# 3_6_1--esp32_-.net
KiCad netlist of a schematic drawn in EasyEDA Pro
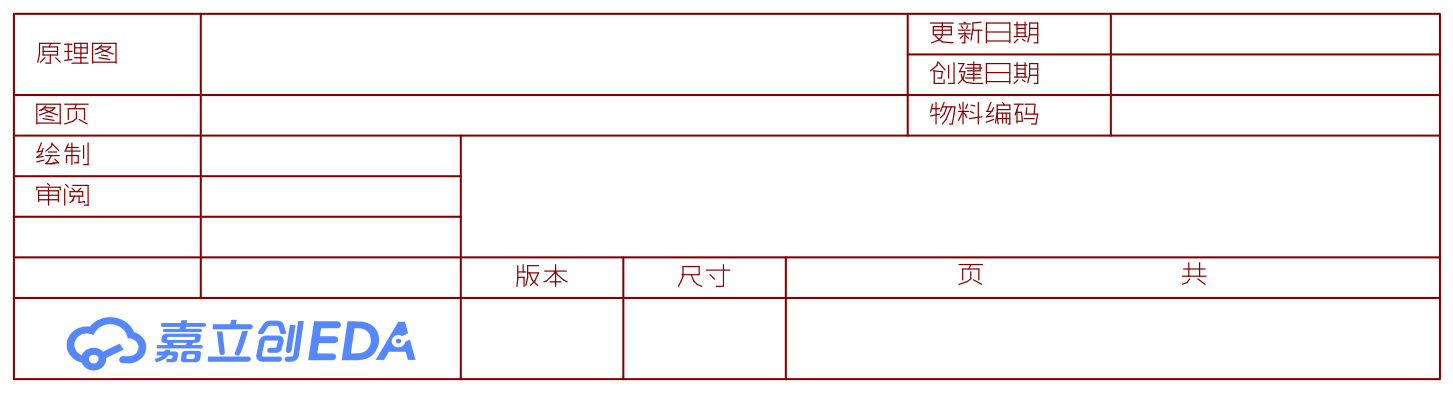
[diagram p0: 主控MCU]
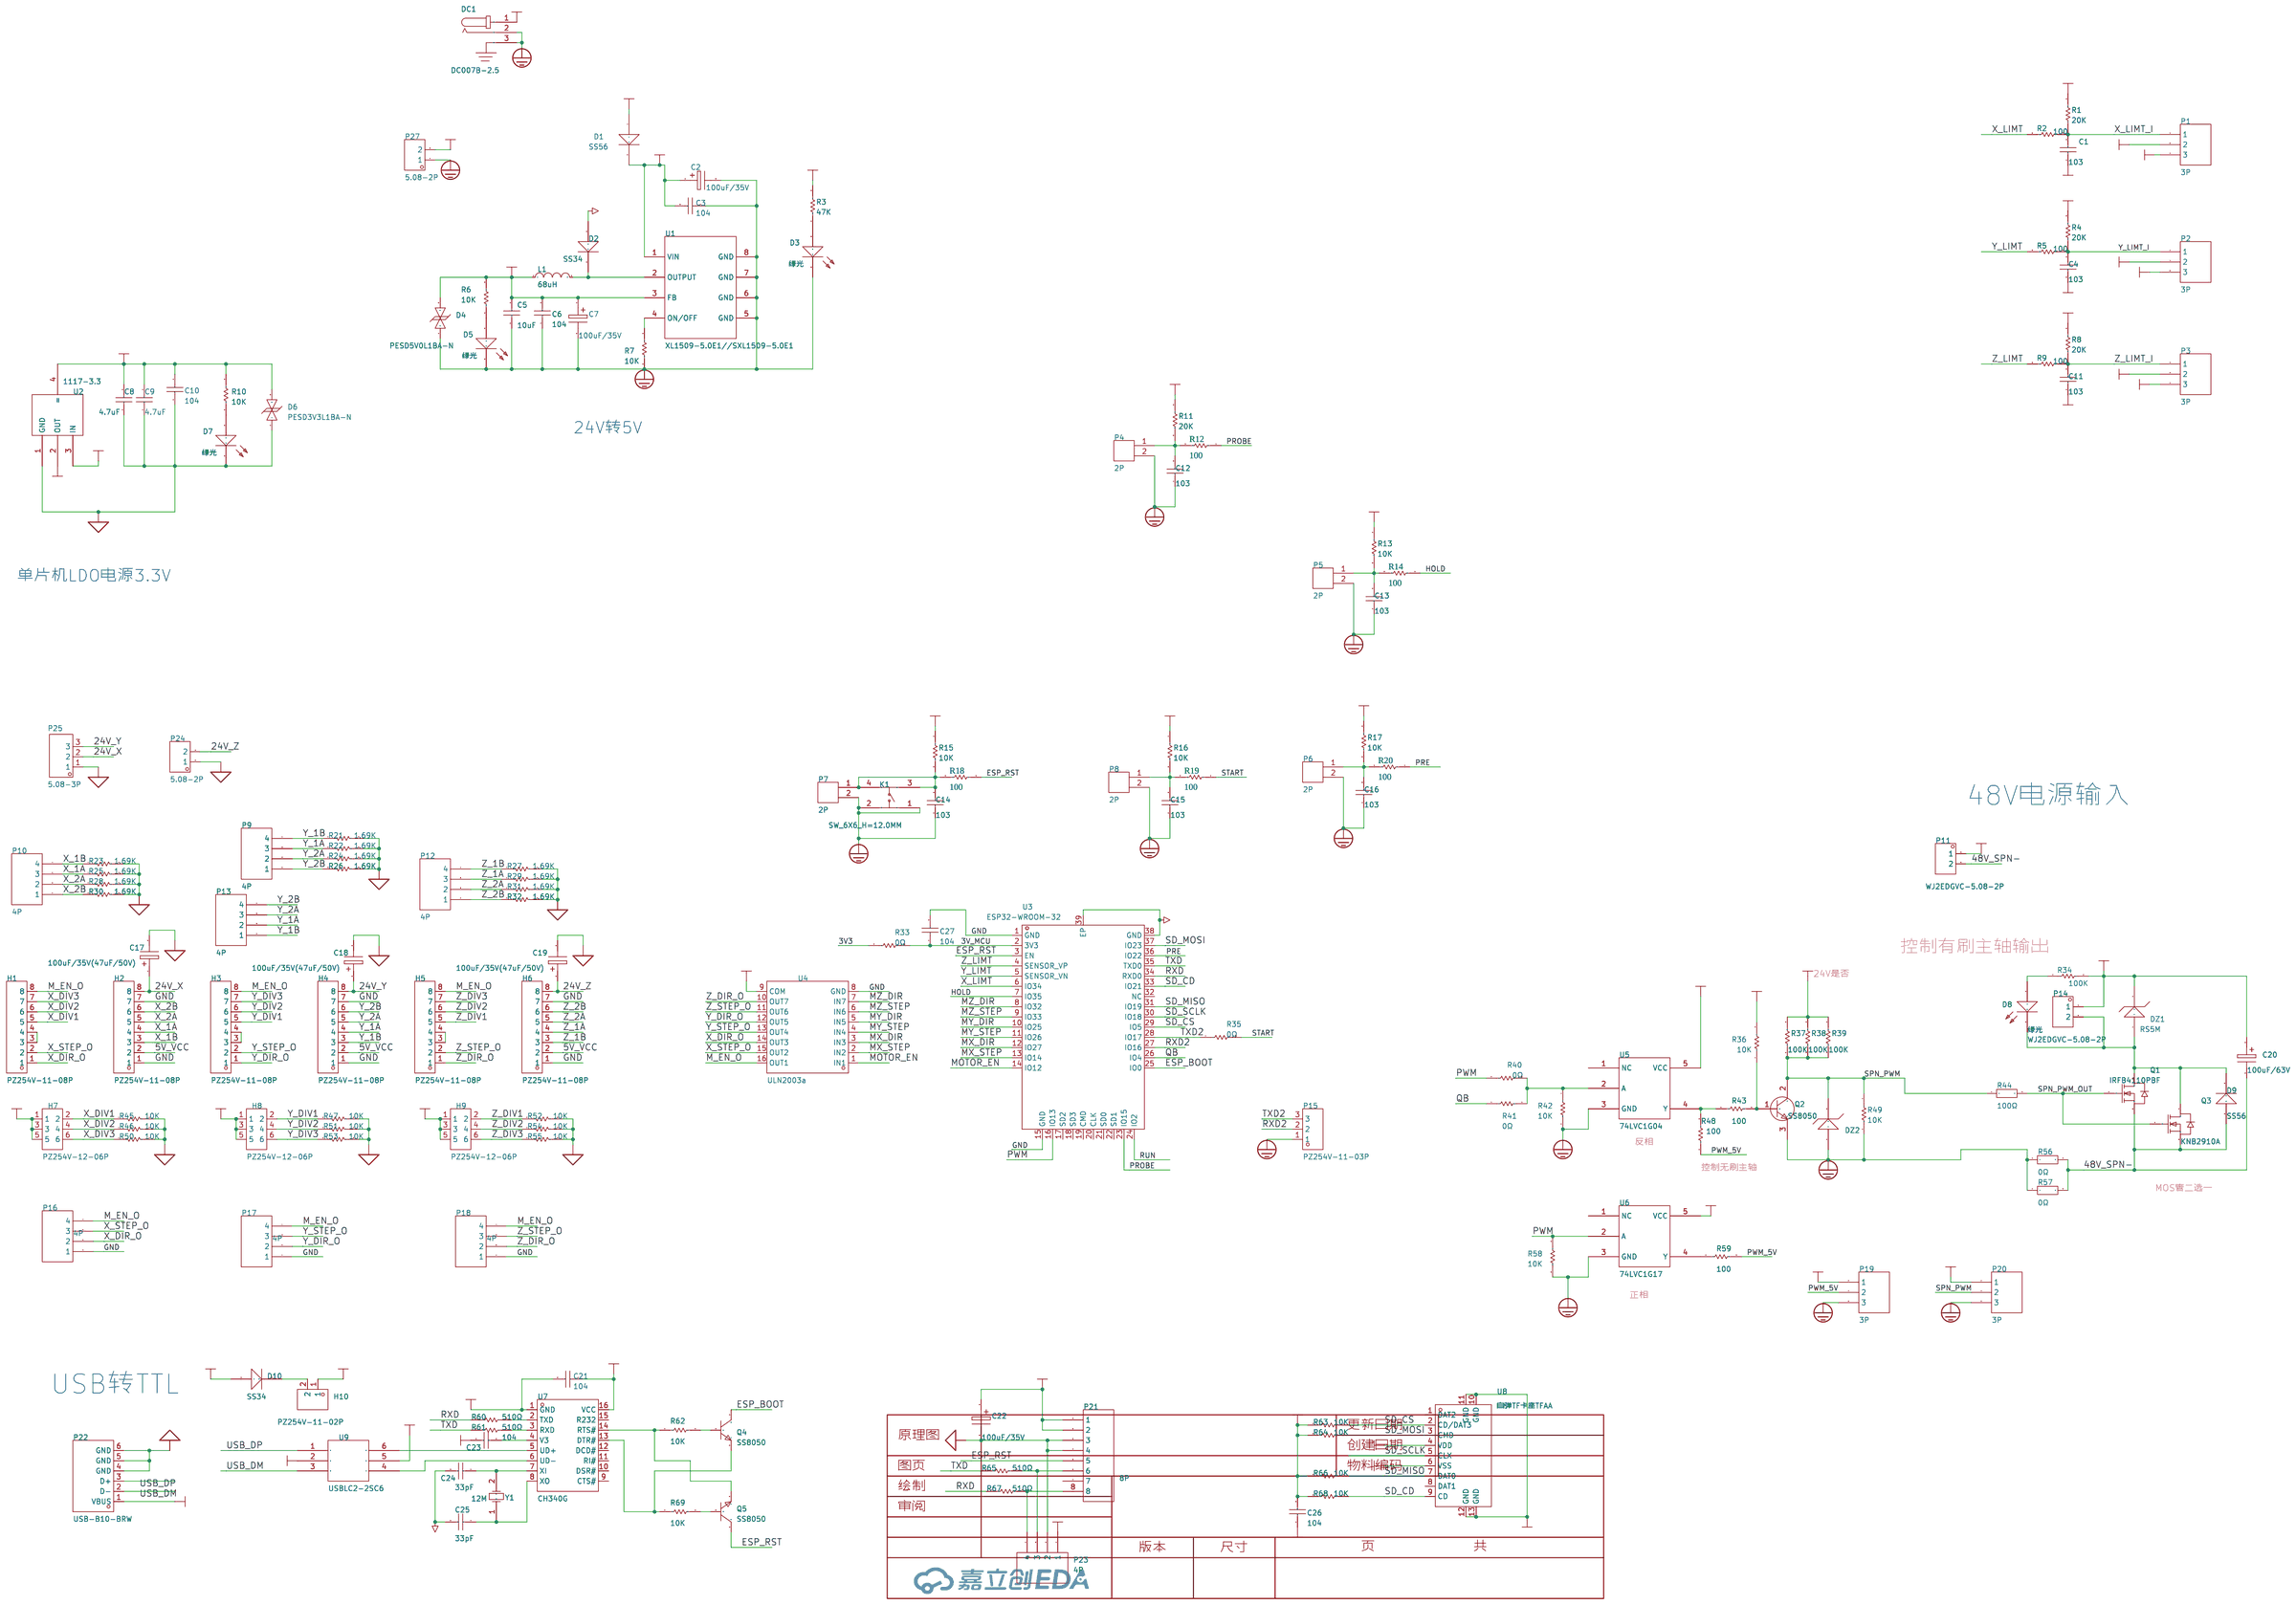
[diagram p1: 电源]

(export (version "E")
  (design (tool "Eeschema 10.0.6"))
  (components
    (comp (ref "C1") (value "103") (footprint "easyedapro:11") (libsource (lib "easyedapro") (part "CAP")))
    (comp (ref "C2")
      (value "100uF/35V")
      (footprint "easyedapro:电解电容贴片10x10")
      (libsource (lib "easyedapro") (part "ELECTRO1"))
    )
    (comp (ref "C3")
      (value "104")
      (footprint "easyedapro:0603C")
      (description "Capacitor (Semiconductor SIM Model)")
      (libsource (lib "easyedapro") (part "Cap Semi"))
    )
    (comp (ref "C4") (value "103") (footprint "easyedapro:11") (libsource (lib "easyedapro") (part "CAP")))
    (comp (ref "C5") (value "10uF") (libsource (lib "") (part "CAP_1")))
    (comp (ref "C6")
      (value "104")
      (footprint "easyedapro:0603C")
      (description "Capacitor (Semiconductor SIM Model)")
      (libsource (lib "easyedapro") (part "Cap Semi"))
    )
    (comp (ref "C7")
      (value "100uF/35V")
      (footprint "easyedapro:0603C")
      (libsource (lib "easyedapro") (part "ELECTRO1"))
    )
    (comp (ref "C8") (value "4.7uF") (libsource (lib "") (part "CAP_1")))
    (comp (ref "C9") (value "4.7uF") (libsource (lib "") (part "CAP_1")))
    (comp (ref "C10")
      (value "104")
      (footprint "easyedapro:0603C")
      (description "Capacitor (Semiconductor SIM Model)")
      (libsource (lib "easyedapro") (part "Cap Semi"))
    )
    (comp (ref "C11") (value "103") (footprint "easyedapro:11") (libsource (lib "easyedapro") (part "CAP")))
    (comp (ref "C12") (value "103") (footprint "easyedapro:11") (libsource (lib "easyedapro") (part "CAP")))
    (comp (ref "C13") (value "103") (footprint "easyedapro:11") (libsource (lib "easyedapro") (part "CAP")))
    (comp (ref "C14") (value "103") (footprint "easyedapro:11") (libsource (lib "easyedapro") (part "CAP")))
    (comp (ref "C15") (value "103") (footprint "easyedapro:11") (libsource (lib "easyedapro") (part "CAP")))
    (comp (ref "C16") (value "103") (footprint "easyedapro:11") (libsource (lib "easyedapro") (part "CAP")))
    (comp (ref "C17")
      (value "100uF/35V(47uF/50V)")
      (footprint "easyedapro:电解电容贴片10x10")
      (libsource (lib "easyedapro") (part "ELECTRO1"))
    )
    (comp (ref "C18")
      (value "100uF/35V(47uF/50V)")
      (footprint "easyedapro:电解电容贴片10x10")
      (libsource (lib "easyedapro") (part "ELECTRO1"))
    )
    (comp (ref "C19")
      (value "100uF/35V(47uF/50V)")
      (footprint "easyedapro:电解电容贴片10x10")
      (libsource (lib "easyedapro") (part "ELECTRO1"))
    )
    (comp (ref "C20")
      (value "100uF/63V")
      (footprint "easyedapro:电解电容贴片10x10")
      (libsource (lib "easyedapro") (part "ELECTRO1"))
    )
    (comp (ref "C21")
      (value "104")
      (footprint "easyedapro:0603C")
      (description "Capacitor (Semiconductor SIM Model)")
      (libsource (lib "easyedapro") (part "Cap Semi"))
    )
    (comp (ref "C22")
      (value "100uF/35V")
      (footprint "easyedapro:电解电容贴片10x10")
      (libsource (lib "easyedapro") (part "ELECTRO1"))
    )
    (comp (ref "C23")
      (value "104")
      (footprint "easyedapro:0603C")
      (description "Capacitor (Semiconductor SIM Model)")
      (libsource (lib "easyedapro") (part "Cap Semi"))
    )
    (comp (ref "C24")
      (value "18pF")
      (footprint "easyedapro:0603C")
      (description "Capacitor (Semiconductor SIM Model)")
      (libsource (lib "easyedapro") (part "Cap Semi"))
    )
    (comp (ref "C25")
      (value "18pF")
      (footprint "easyedapro:0603C")
      (description "Capacitor (Semiconductor SIM Model)")
      (libsource (lib "easyedapro") (part "Cap Semi"))
    )
    (comp (ref "C26")
      (value "104")
      (footprint "easyedapro:11")
      (description "Capacitor (Semiconductor SIM Model)")
      (libsource (lib "easyedapro") (part "Cap Semi"))
    )
    (comp (ref "C27")
      (value "104")
      (footprint "easyedapro:0603C")
      (description "Capacitor (Semiconductor SIM Model)")
      (libsource (lib "easyedapro") (part "Cap Semi"))
    )
    (comp (ref "D1")
      (value "SS56")
      (footprint "easyedapro:SMA")
      (libsource (lib "easyedapro") (part "1N4148"))
    )
    (comp (ref "D2") (value "SS34") (libsource (lib "") (part "1N4148_1")))
    (comp (ref "D3")
      (value "绿光")
      (footprint "easyedapro:0603LED")
      (libsource (lib "easyedapro") (part "LED"))
    )
    (comp (ref "D4")
      (value "PESD5V0L1BA-N")
      (footprint "easyedapro:SOD-523_L1.2-W0.8-LS1.6-BI")
      (description "极性:Bidirectional;反向关断电压（典型值）:5V (Max);击穿电压（最小值）:6V;箝位电压:15V;峰值脉冲电流（10/1000us）:5A (8/20us);")
      (fields (field (name "Manufacturer") "BORN伯恩半导体"))
      (libsource (lib "easyedapro") (part "PESD5V0S1BBN"))
    )
    (comp (ref "D5")
      (value "绿光")
      (footprint "easyedapro:0603LED")
      (libsource (lib "easyedapro") (part "LED"))
    )
    (comp (ref "D6")
      (value "PESD3V3L1BA-N")
      (footprint "easyedapro:SOD-523_L1.2-W0.8-LS1.6-BI")
      (description "极性:Bidirectional;反向关断电压（典型值）:5V (Max);击穿电压（最小值）:6V;箝位电压:15V;峰值脉冲电流（10/1000us）:5A (8/20us);")
      (fields (field (name "Manufacturer") "BORN伯恩半导体"))
      (libsource (lib "easyedapro") (part "PESD5V0S1BBN"))
    )
    (comp (ref "D7")
      (value "绿光")
      (footprint "easyedapro:0603LED")
      (libsource (lib "easyedapro") (part "LED"))
    )
    (comp (ref "D8")
      (value "绿光")
      (footprint "easyedapro:0603LED")
      (libsource (lib "easyedapro") (part "LED"))
    )
    (comp (ref "D9") (value "SS56") (libsource (lib "") (part "1N4148_1")))
    (comp (ref "D10")
      (value "SS34")
      (footprint "easyedapro:SMA")
      (libsource (lib "easyedapro") (part "1N4148"))
    )
    (comp (ref "DC1")
      (value "DC007B-2.5")
      (footprint "easyedapro:DC-IN-TH_HX-DC007B-2.5")
      (description "连接器类型:DC电源插座;安装方式:弯插;触点内径:2.5mm;触点外径:7.7mm;额定电流:5A;额定电压:20V;工作温度:-25°C~+70°C;")
      (fields (field (name "Manufacturer") "SHOU HAN(首韩)"))
      (libsource (lib "easyedapro") (part "DC007B-2.5"))
    )
    (comp (ref "DZ1") (value "RS5M") (libsource (lib "easyedapro") (part "ѹ")))
    (comp (ref "DZ2") (value "--ѹ------SMAZ10V") (libsource (lib "easyedapro") (part "ѹ")))
    (comp (ref "H1")
      (value "PZ254V-11-08P")
      (footprint "easyedapro:HDR-TH_8P-P2.54-V-M")
      (fields (field (name "Manufacturer") "XFCN(兴飞)"))
      (libsource (lib "easyedapro") (part "PZ254V-11-08P"))
    )
    (comp (ref "H2")
      (value "PZ254V-11-08P")
      (footprint "easyedapro:HDR-TH_8P-P2.54-V-M")
      (fields (field (name "Manufacturer") "XFCN(兴飞)"))
      (libsource (lib "easyedapro") (part "PZ254V-11-08P"))
    )
    (comp (ref "H3")
      (value "PZ254V-11-08P")
      (footprint "easyedapro:HDR-TH_8P-P2.54-V-M")
      (fields (field (name "Manufacturer") "XFCN(兴飞)"))
      (libsource (lib "easyedapro") (part "PZ254V-11-08P"))
    )
    (comp (ref "H4")
      (value "PZ254V-11-08P")
      (footprint "easyedapro:HDR-TH_8P-P2.54-V-M")
      (fields (field (name "Manufacturer") "XFCN(兴飞)"))
      (libsource (lib "easyedapro") (part "PZ254V-11-08P"))
    )
    (comp (ref "H5")
      (value "PZ254V-11-08P")
      (footprint "easyedapro:HDR-TH_8P-P2.54-V-M")
      (fields (field (name "Manufacturer") "XFCN(兴飞)"))
      (libsource (lib "easyedapro") (part "PZ254V-11-08P"))
    )
    (comp (ref "H6")
      (value "PZ254V-11-08P")
      (footprint "easyedapro:HDR-TH_8P-P2.54-V-M")
      (fields (field (name "Manufacturer") "XFCN(兴飞)"))
      (libsource (lib "easyedapro") (part "PZ254V-11-08P"))
    )
    (comp (ref "H7")
      (value "PZ254V-12-06P")
      (footprint "easyedapro:HDR-TH_PZ254V-12-06P-A40")
      (description "排针2.54mm间距 直插 2x03位 直针外露4mm")
      (fields (field (name "Manufacturer") "XFCN(兴飞)"))
      (libsource (lib "easyedapro") (part "PZ254V-12-06P-A40"))
    )
    (comp (ref "H8")
      (value "PZ254V-12-06P")
      (footprint "easyedapro:HDR-TH_PZ254V-12-06P-A40")
      (description "排针2.54mm间距 直插 2x03位 直针外露4mm")
      (fields (field (name "Manufacturer") "XFCN(兴飞)"))
      (libsource (lib "easyedapro") (part "PZ254V-12-06P-A40"))
    )
    (comp (ref "H9")
      (value "PZ254V-12-06P")
      (footprint "easyedapro:HDR-TH_PZ254V-12-06P-A40")
      (description "排针2.54mm间距 直插 2x03位 直针外露4mm")
      (fields (field (name "Manufacturer") "XFCN(兴飞)"))
      (libsource (lib "easyedapro") (part "PZ254V-12-06P-A40"))
    )
    (comp (ref "H10")
      (value "PZ254V-11-02P")
      (footprint "easyedapro:HDR-TH_2P-P2.54-V-M")
      (fields (field (name "Manufacturer") "XFCN(兴飞)"))
      (libsource (lib "easyedapro") (part "PZ254V-11-02P"))
    )
    (comp (ref "K1")
      (value "SW_6X6_H=12.0MM")
      (footprint "easyedapro:KEY-SMD_4P-L6.0-W6.0-P4.50-LS9.0")
      (libsource (lib "easyedapro") (part "SW_6X6_H=12.0MM"))
    )
    (comp (ref "L1")
      (value "68uH")
      (footprint "easyedapro:IND-SMD_L7.0-W7.0_SMDRI74-330MT")
      (description "电感值:33uH;精度:±20%;额定电流:960mA;饱和电流(Isat):1.8A;类型:屏蔽电感;")
      (fields (field (name "Manufacturer Part") "SMDRI74-330MT") (field (name "Manufacturer") "SXN(顺翔诺)"))
      (libsource (lib "easyedapro") (part "SMDRI74-330MT"))
    )
    (comp (ref "P1")
      (value "3P")
      (footprint "easyedapro:HDR1X3_CON")
      (libsource (lib "easyedapro") (part "3P"))
    )
    (comp (ref "P2")
      (value "3P")
      (footprint "easyedapro:HDR1X3_CON")
      (libsource (lib "easyedapro") (part "3P"))
    )
    (comp (ref "P3")
      (value "3P")
      (footprint "easyedapro:HDR1X3_CON")
      (libsource (lib "easyedapro") (part "3P"))
    )
    (comp (ref "P4") (value "2P") (libsource (lib "easyedapro") (part "2P")))
    (comp (ref "P5") (value "2P") (libsource (lib "easyedapro") (part "2P")))
    (comp (ref "P6") (value "2P") (libsource (lib "easyedapro") (part "2P")))
    (comp (ref "P7") (value "2P") (libsource (lib "easyedapro") (part "2P")))
    (comp (ref "P8") (value "2P") (libsource (lib "easyedapro") (part "2P")))
    (comp (ref "P9")
      (value "4P")
      (footprint "easyedapro:HDR1X4_CON")
      (libsource (lib "easyedapro") (part "4P"))
    )
    (comp (ref "P10")
      (value "4P")
      (footprint "easyedapro:HDR1X4_CON")
      (libsource (lib "easyedapro") (part "4P"))
    )
    (comp (ref "P11")
      (value "WJ2EDGVC-5.08-2P")
      (footprint "easyedapro:CONN-TH_WJ2EDGVC-5.08-2P")
      (fields (field (name "Manufacturer") "KANGNEX(康奈克斯电气)"))
      (libsource (lib "easyedapro") (part "WJ2EDGVC-5.08-2P"))
    )
    (comp (ref "P12")
      (value "4P")
      (footprint "easyedapro:HDR1X4_CON")
      (libsource (lib "easyedapro") (part "4P"))
    )
    (comp (ref "P13")
      (value "4P")
      (footprint "easyedapro:HDR1X4_CON")
      (libsource (lib "easyedapro") (part "4P"))
    )
    (comp (ref "P14")
      (value "WJ2EDGVC-5.08-2P")
      (footprint "easyedapro:CONN-TH_WJ2EDGVC-5.08-2P")
      (fields (field (name "Manufacturer") "KANGNEX(康奈克斯电气)"))
      (libsource (lib "easyedapro") (part "WJ2EDGVC-5.08-2P"))
    )
    (comp (ref "P15")
      (value "PZ254V-11-03P")
      (footprint "easyedapro:HDR-TH_3P-P2.54-V-M")
      (fields (field (name "Manufacturer") "XFCN(兴飞)"))
      (libsource (lib "easyedapro") (part "PZ254V-11-03P_C2937625"))
    )
    (comp (ref "P16") (value "4P") (libsource (lib "") (part "4P_1")))
    (comp (ref "P17") (value "4P") (libsource (lib "") (part "4P_1")))
    (comp (ref "P18") (value "4P") (libsource (lib "") (part "4P_1")))
    (comp (ref "P19")
      (value "3P")
      (footprint "easyedapro:HDR1X3_CON")
      (libsource (lib "easyedapro") (part "3P"))
    )
    (comp (ref "P20")
      (value "3P")
      (footprint "easyedapro:HDR1X3_CON")
      (libsource (lib "easyedapro") (part "3P"))
    )
    (comp (ref "P21") (value "8P") (footprint "easyedapro:IDC8") (libsource (lib "easyedapro") (part "8P")))
    (comp (ref "P22")
      (value "USB-B10-BRW")
      (footprint "easyedapro:USB-B-TH_USB-B10-BRW")
      (fields (field (name "Manufacturer") "XUNPU(讯普)"))
      (libsource (lib "easyedapro") (part "USB-B10-BRW"))
    )
    (comp (ref "P23")
      (value "4P")
      (footprint "easyedapro:HDR1X4_CON")
      (libsource (lib "easyedapro") (part "4P"))
    )
    (comp (ref "P24")
      (value "5.08-2P")
      (footprint "easyedapro:CONN-TH_WJ2EDGVC-5.08-2P")
      (fields (field (name "Manufacturer") "KANGNEX(康奈克斯电气)"))
      (libsource (lib "easyedapro") (part "WJ2EDGVC-5.08-2P"))
    )
    (comp (ref "P25")
      (value "5.08-3P")
      (footprint "easyedapro:CONN-TH_3P-P5.08-WJ2EDGVC-3P")
      (description "连接器类型:板端/插座-闭口;间距:5.08mm;排数:1;每排PIN数:3;安装方式:直针;颜色:绿色;")
      (fields (field (name "Manufacturer") "KANGNEX(康奈克斯电气)"))
      (libsource (lib "easyedapro") (part "WJ2EDGVC-3P"))
    )
    (comp (ref "P27")
      (value "5.08-2P")
      (footprint "easyedapro:CONN-TH_WJ2EDGVC-5.08-2P")
      (fields (field (name "Manufacturer") "KANGNEX(康奈克斯电气)"))
      (libsource (lib "easyedapro") (part "WJ2EDGVC-5.08-2P"))
    )
    (comp (ref "Q1")
      (value "IRFB4110PBF")
      (footprint "easyedapro:TO-220-3_L10.0-W4.5-P2.54-L")
      (fields (field (name "Manufacturer") "Infineon(英飞凌)"))
      (libsource (lib "easyedapro") (part "IRFB4110PBF"))
    )
    (comp (ref "Q2")
      (value "SS8050")
      (fields (field (name "Publisher") "Altium Limited"))
      (libsource (lib "easyedapro") (part "NPN"))
    )
    (comp (ref "Q3")
      (value "KNB2910A")
      (footprint "easyedapro:TO-263-2_L10.0-W9.1-P5.08-LS15.2-TL")
      (description "类型:-;漏源电压(Vdss):100V;连续漏极电流(Id):130A;导通电阻(RDS(on)):9mΩ@70V,10A;耗散功率(Pd):300W;阈值电压(Vgs(th)):4V;")
      (fields (field (name "Manufacturer") "KIA"))
      (libsource (lib "easyedapro") (part "KNB2910A"))
    )
    (comp (ref "Q4")
      (value "SS8050")
      (footprint "easyedapro:SOT-23-3_L2.9-W1.3-P1.90-LS2.4-BR")
      (fields (field (name "Manufacturer") "Doeshare(德芯)"))
      (libsource (lib "easyedapro") (part "SS8050_C2931717"))
    )
    (comp (ref "Q5")
      (value "SS8050")
      (footprint "easyedapro:SOT-23-3_L2.9-W1.3-P1.90-LS2.4-BR")
      (fields (field (name "Manufacturer") "Doeshare(德芯)"))
      (libsource (lib "easyedapro") (part "SS8050_C2931717"))
    )
    (comp (ref "R1")
      (value "20K")
      (footprint "easyedapro:10")
      (description "Resistor")
      (libsource (lib "easyedapro") (part "RES"))
    )
    (comp (ref "R2")
      (value "100")
      (footprint "easyedapro:10")
      (description "Resistor")
      (libsource (lib "easyedapro") (part "RES"))
    )
    (comp (ref "R3")
      (value "47K")
      (footprint "easyedapro:0603R")
      (description "Resistor")
      (libsource (lib "easyedapro") (part "RES"))
    )
    (comp (ref "R4")
      (value "20K")
      (footprint "easyedapro:10")
      (description "Resistor")
      (libsource (lib "easyedapro") (part "RES"))
    )
    (comp (ref "R5")
      (value "100")
      (footprint "easyedapro:10")
      (description "Resistor")
      (libsource (lib "easyedapro") (part "RES"))
    )
    (comp (ref "R6")
      (value "10K")
      (footprint "easyedapro:0603R")
      (description "Resistor")
      (libsource (lib "easyedapro") (part "RES"))
    )
    (comp (ref "R7")
      (value "10K")
      (footprint "easyedapro:0603R")
      (description "Resistor")
      (libsource (lib "easyedapro") (part "RES"))
    )
    (comp (ref "R8")
      (value "20K")
      (footprint "easyedapro:10")
      (description "Resistor")
      (libsource (lib "easyedapro") (part "RES"))
    )
    (comp (ref "R9")
      (value "100")
      (footprint "easyedapro:10")
      (description "Resistor")
      (libsource (lib "easyedapro") (part "RES"))
    )
    (comp (ref "R10")
      (value "10K")
      (footprint "easyedapro:0603R")
      (description "Resistor")
      (libsource (lib "easyedapro") (part "RES"))
    )
    (comp (ref "R11")
      (value "10K")
      (footprint "easyedapro:0603R")
      (description "Resistor")
      (libsource (lib "easyedapro") (part "RES"))
    )
    (comp (ref "R12")
      (value "100")
      (description "Resistor")
      (fields (field (name "Publisher") "Altium Limited"))
      (libsource (lib "") (part "RES_1"))
    )
    (comp (ref "R13")
      (value "10K")
      (footprint "easyedapro:0603R")
      (description "Resistor")
      (libsource (lib "easyedapro") (part "RES"))
    )
    (comp (ref "R14")
      (value "100")
      (description "Resistor")
      (fields (field (name "Publisher") "Altium Limited"))
      (libsource (lib "") (part "RES_1"))
    )
    (comp (ref "R15")
      (value "10K")
      (footprint "easyedapro:0603R")
      (description "Resistor")
      (libsource (lib "easyedapro") (part "RES"))
    )
    (comp (ref "R16")
      (value "10K")
      (footprint "easyedapro:0603R")
      (description "Resistor")
      (libsource (lib "easyedapro") (part "RES"))
    )
    (comp (ref "R17")
      (value "10K")
      (footprint "easyedapro:0603R")
      (description "Resistor")
      (libsource (lib "easyedapro") (part "RES"))
    )
    (comp (ref "R18")
      (value "100")
      (description "Resistor")
      (fields (field (name "Publisher") "Altium Limited"))
      (libsource (lib "") (part "RES_1"))
    )
    (comp (ref "R19")
      (value "100")
      (description "Resistor")
      (fields (field (name "Publisher") "Altium Limited"))
      (libsource (lib "") (part "RES_1"))
    )
    (comp (ref "R20")
      (value "100")
      (description "Resistor")
      (fields (field (name "Publisher") "Altium Limited"))
      (libsource (lib "") (part "RES_1"))
    )
    (comp (ref "R21")
      (value "10K")
      (footprint "easyedapro:0603R")
      (description "Resistor")
      (libsource (lib "easyedapro") (part "10K"))
    )
    (comp (ref "R22")
      (value "10K")
      (footprint "easyedapro:0603R")
      (description "Resistor")
      (libsource (lib "easyedapro") (part "10K"))
    )
    (comp (ref "R23")
      (value "10K")
      (footprint "easyedapro:0603R")
      (description "Resistor")
      (libsource (lib "easyedapro") (part "10K"))
    )
    (comp (ref "R24")
      (value "10K")
      (footprint "easyedapro:0603R")
      (description "Resistor")
      (libsource (lib "easyedapro") (part "10K"))
    )
    (comp (ref "R25")
      (value "10K")
      (footprint "easyedapro:0603R")
      (description "Resistor")
      (libsource (lib "easyedapro") (part "10K"))
    )
    (comp (ref "R26")
      (value "10K")
      (footprint "easyedapro:0603R")
      (description "Resistor")
      (libsource (lib "easyedapro") (part "10K"))
    )
    (comp (ref "R27")
      (value "10K")
      (footprint "easyedapro:0603R")
      (description "Resistor")
      (libsource (lib "easyedapro") (part "10K"))
    )
    (comp (ref "R28")
      (value "10K")
      (footprint "easyedapro:0603R")
      (description "Resistor")
      (libsource (lib "easyedapro") (part "10K"))
    )
    (comp (ref "R29")
      (value "10K")
      (footprint "easyedapro:0603R")
      (description "Resistor")
      (libsource (lib "easyedapro") (part "10K"))
    )
    (comp (ref "R30")
      (value "10K")
      (footprint "easyedapro:0603R")
      (description "Resistor")
      (libsource (lib "easyedapro") (part "10K"))
    )
    (comp (ref "R31")
      (value "10K")
      (footprint "easyedapro:0603R")
      (description "Resistor")
      (libsource (lib "easyedapro") (part "10K"))
    )
    (comp (ref "R32")
      (value "10K")
      (footprint "easyedapro:0603R")
      (description "Resistor")
      (libsource (lib "easyedapro") (part "10K"))
    )
    (comp (ref "R33")
      (value "0Ω")
      (description "Resistor")
      (fields (field (name "Publisher") "Altium Limited"))
      (libsource (lib "") (part "RES_1"))
    )
    (comp (ref "R34")
      (value "100K")
      (description "Resistor")
      (fields (field (name "Publisher") "Altium Limited"))
      (libsource (lib "") (part "RES_1"))
    )
    (comp (ref "R35")
      (value "0Ω")
      (description "Resistor")
      (fields (field (name "Publisher") "Altium Limited"))
      (libsource (lib "") (part "RES_1"))
    )
    (comp (ref "R36")
      (value "10K")
      (description "Resistor")
      (fields (field (name "Publisher") "Altium Limited"))
      (libsource (lib "") (part "RES_1"))
    )
    (comp (ref "R37")
      (value "100K")
      (description "Resistor")
      (fields (field (name "Publisher") "Altium Limited"))
      (libsource (lib "") (part "RES_1"))
    )
    (comp (ref "R38")
      (value "100K")
      (description "Resistor")
      (fields (field (name "Publisher") "Altium Limited"))
      (libsource (lib "") (part "RES_1"))
    )
    (comp (ref "R39")
      (value "100K")
      (description "Resistor")
      (fields (field (name "Publisher") "Altium Limited"))
      (libsource (lib "") (part "RES_1"))
    )
    (comp (ref "R40")
      (value "0Ω")
      (description "Resistor")
      (fields (field (name "Publisher") "Altium Limited"))
      (libsource (lib "") (part "RES_1"))
    )
    (comp (ref "R41")
      (value "0Ω")
      (description "Resistor")
      (fields (field (name "Publisher") "Altium Limited"))
      (libsource (lib "") (part "RES_1"))
    )
    (comp (ref "R42")
      (value "10K")
      (description "Resistor")
      (fields (field (name "Publisher") "Altium Limited"))
      (libsource (lib "") (part "RES_1"))
    )
    (comp (ref "R43")
      (value "100")
      (description "Resistor")
      (fields (field (name "Publisher") "Altium Limited"))
      (libsource (lib "") (part "RES_1"))
    )
    (comp (ref "R44")
      (value "100Ω")
      (footprint "easyedapro:R1210")
      (libsource (lib "easyedapro") (part "电阻"))
    )
    (comp (ref "R45")
      (value "10K")
      (footprint "easyedapro:0603R")
      (description "Resistor")
      (libsource (lib "easyedapro") (part "10K"))
    )
    (comp (ref "R46")
      (value "10K")
      (footprint "easyedapro:0603R")
      (description "Resistor")
      (libsource (lib "easyedapro") (part "10K"))
    )
    (comp (ref "R47")
      (value "10K")
      (footprint "easyedapro:0603R")
      (description "Resistor")
      (libsource (lib "easyedapro") (part "10K"))
    )
    (comp (ref "R48")
      (value "100")
      (description "Resistor")
      (fields (field (name "Publisher") "Altium Limited"))
      (libsource (lib "") (part "RES_1"))
    )
    (comp (ref "R49")
      (value "10K")
      (description "Resistor")
      (fields (field (name "Publisher") "Altium Limited"))
      (libsource (lib "") (part "RES_1"))
    )
    (comp (ref "R50")
      (value "10K")
      (footprint "easyedapro:0603R")
      (description "Resistor")
      (libsource (lib "easyedapro") (part "10K"))
    )
    (comp (ref "R51")
      (value "10K")
      (footprint "easyedapro:0603R")
      (description "Resistor")
      (libsource (lib "easyedapro") (part "10K"))
    )
    (comp (ref "R52")
      (value "10K")
      (footprint "easyedapro:0603R")
      (description "Resistor")
      (libsource (lib "easyedapro") (part "10K"))
    )
    (comp (ref "R53")
      (value "10K")
      (footprint "easyedapro:0603R")
      (description "Resistor")
      (libsource (lib "easyedapro") (part "10K"))
    )
    (comp (ref "R54")
      (value "10K")
      (footprint "easyedapro:0603R")
      (description "Resistor")
      (libsource (lib "easyedapro") (part "10K"))
    )
    (comp (ref "R55")
      (value "10K")
      (footprint "easyedapro:0603R")
      (description "Resistor")
      (libsource (lib "easyedapro") (part "10K"))
    )
    (comp (ref "R56") (value "0Ω") (footprint "easyedapro:R1210") (libsource (lib "easyedapro") (part "电阻")))
    (comp (ref "R57") (value "0Ω") (footprint "easyedapro:R1210") (libsource (lib "easyedapro") (part "电阻")))
    (comp (ref "R58")
      (value "10K")
      (description "Resistor")
      (fields (field (name "Publisher") "Altium Limited"))
      (libsource (lib "") (part "RES_1"))
    )
    (comp (ref "R59")
      (value "100")
      (description "Resistor")
      (fields (field (name "Publisher") "Altium Limited"))
      (libsource (lib "") (part "RES_1"))
    )
    (comp (ref "R60")
      (value "510Ω")
      (footprint "easyedapro:0603R")
      (description "Resistor")
      (libsource (lib "easyedapro") (part "RES"))
    )
    (comp (ref "R61")
      (value "510Ω")
      (footprint "easyedapro:0603R")
      (description "Resistor")
      (libsource (lib "easyedapro") (part "RES"))
    )
    (comp (ref "R62")
      (value "10K")
      (footprint "easyedapro:0603R")
      (description "Resistor")
      (libsource (lib "easyedapro") (part "RES"))
    )
    (comp (ref "R63")
      (value "10K")
      (footprint "easyedapro:10")
      (description "Resistor")
      (libsource (lib "easyedapro") (part "RES"))
    )
    (comp (ref "R64")
      (value "10K")
      (footprint "easyedapro:10")
      (description "Resistor")
      (libsource (lib "easyedapro") (part "RES"))
    )
    (comp (ref "R65")
      (value "510Ω")
      (footprint "easyedapro:0603R")
      (description "Resistor")
      (libsource (lib "easyedapro") (part "RES"))
    )
    (comp (ref "R66")
      (value "10K")
      (footprint "easyedapro:10")
      (description "Resistor")
      (libsource (lib "easyedapro") (part "RES"))
    )
    (comp (ref "R67")
      (value "510Ω")
      (footprint "easyedapro:0603R")
      (description "Resistor")
      (libsource (lib "easyedapro") (part "RES"))
    )
    (comp (ref "R68")
      (value "10K")
      (footprint "easyedapro:10")
      (description "Resistor")
      (libsource (lib "easyedapro") (part "RES"))
    )
    (comp (ref "R69")
      (value "10K")
      (footprint "easyedapro:0603R")
      (description "Resistor")
      (libsource (lib "easyedapro") (part "RES"))
    )
    (comp (ref "U1")
      (value "XL1509-5.0E1//SXL1509-5.0E1")
      (footprint "easyedapro:SOIC-8_L5.0-W4.0-P1.27-LS6.0-BL")
      (description "功能类型:降压型;同步整流:-;输出通道数:-;拓扑结构:-;输入电压:-;输出电流(最大值):-;开关频率:-;")
      (fields (field (name "Manufacturer") "XLSEMI(芯龙)"))
      (libsource (lib "easyedapro") (part "XL1509-5.0E1"))
    )
    (comp (ref "U2")
      (value "1117-3.3")
      (footprint "easyedapro:SOT-223")
      (libsource (lib "easyedapro") (part "LM1117"))
    )
    (comp (ref "U3")
      (value "ESP32-WROOM-32")
      (footprint "easyedapro:WIFIM-SMD_ESP-WROOM-32")
      (description "WiFi+双模蓝牙 双核CPU 网口 顶配MCU 低功耗蓝牙 ESP32系列ESP-WROOM-32模组/ESP-32S 4MB")
      (fields (field (name "Manufacturer") "ESPRESSIF(乐鑫)"))
      (libsource (lib "easyedapro") (part "ESP-WROOM-32"))
    )
    (comp (ref "U4")
      (value "ULN2003a")
      (footprint "easyedapro:SOP-16_L9.9-W3.9-P1.27-LS6.0-BL")
      (description "通道数:七路;集射击穿电压(Vceo):50V;集电极电流(Ic):500mA;")
      (fields (field (name "Manufacturer") "GR(国睿)"))
      (libsource (lib "easyedapro") (part "ULN2003_C18164408"))
    )
    (comp (ref "U5")
      (value "74LVC1G04")
      (footprint "easyedapro:SMD8")
      (libsource (lib "easyedapro") (part "74LVC1G04"))
    )
    (comp (ref "U6")
      (value "74LVC1G17")
      (footprint "easyedapro:SMD8")
      (libsource (lib "easyedapro") (part "74LVC1G04"))
    )
    (comp (ref "U7")
      (value "CH340G")
      (footprint "easyedapro:SOIC-16_L9.9-W3.9-P1.27-LS6.0-BL")
      (description "应用功能:收发器;接口协议:USB 2.0;数据速率:2Mbps;")
      (fields (field (name "Manufacturer") "WCH(南京沁恒)"))
      (libsource (lib "easyedapro") (part "CH340G"))
    )
    (comp (ref "U8")
      (value "自弹TF卡座TFAA")
      (footprint "easyedapro:SIM-SMD_C9900015645")
      (libsource (lib "easyedapro") (part "自弹TF卡座TFAA"))
    )
    (comp (ref "U9")
      (value "USBLC2-2SC6")
      (footprint "easyedapro:SOT-23-6")
      (libsource (lib "easyedapro") (part "DIP6"))
    )
    (comp (ref "Y1")
      (value "12M")
      (footprint "easyedapro:晶振贴片49SSMD")
      (description "Crystal Oscillator")
      (libsource (lib "easyedapro") (part "XTAL"))
    )
  )
  (nets
    (net (code "1") (name "3V3") (class "Default")
      (node (ref "C10") (pin "2") (pinfunction "2_2") (pintype "unspecified"))
      (node (ref "C26") (pin "2") (pinfunction "2_2") (pintype "unspecified"))
      (node (ref "C8") (pin "2") (pinfunction "2_2") (pintype "input"))
      (node (ref "C9") (pin "2") (pinfunction "2_2") (pintype "input"))
      (node (ref "D6") (pin "2") (pinfunction "2_2") (pintype "input"))
      (node (ref "R10") (pin "2") (pinfunction "2_2") (pintype "unspecified"))
      (node (ref "R13") (pin "1") (pinfunction "1_1") (pintype "unspecified"))
      (node (ref "R15") (pin "1") (pinfunction "1_1") (pintype "unspecified"))
      (node (ref "R33") (pin "1") (pinfunction "1_1") (pintype "input"))
      (node (ref "R63") (pin "2") (pinfunction "2_2") (pintype "unspecified"))
      (node (ref "R64") (pin "2") (pinfunction "2_2") (pintype "unspecified"))
      (node (ref "R66") (pin "2") (pinfunction "2_2") (pintype "unspecified"))
      (node (ref "R68") (pin "2") (pinfunction "2_2") (pintype "unspecified"))
      (node (ref "U2") (pin "2") (pinfunction "OUT_2") (pintype "unspecified"))
      (node (ref "U2") (pin "4") (pinfunction "=_4") (pintype "unspecified"))
      (node (ref "U8") (pin "4") (pinfunction "VDD_4") (pintype "unspecified"))
    )
    (net (code "2") (name "3V_MCU") (class "Default")
      (node (ref "C27") (pin "1") (pinfunction "1_1") (pintype "unspecified"))
      (node (ref "R16") (pin "1") (pinfunction "1_1") (pintype "unspecified"))
      (node (ref "R17") (pin "1") (pinfunction "1_1") (pintype "unspecified"))
      (node (ref "R33") (pin "2") (pinfunction "2_2") (pintype "input"))
      (node (ref "U3") (pin "2") (pinfunction "3V3_2") (pintype "unspecified"))
    )
    (net (code "3") (name "5V_VCC") (class "Default")
      (node (ref "C21") (pin "1") (pinfunction "1_1") (pintype "unspecified"))
      (node (ref "C22") (pin "1") (pintype "unspecified"))
      (node (ref "C5") (pin "1") (pinfunction "1_1") (pintype "input"))
      (node (ref "C6") (pin "2") (pinfunction "2_2") (pintype "unspecified"))
      (node (ref "C7") (pin "1") (pintype "unspecified"))
      (node (ref "D4") (pin "2") (pinfunction "2_2") (pintype "input"))
      (node (ref "H10") (pin "1") (pinfunction "1_1") (pintype "unspecified"))
      (node (ref "H2") (pin "2") (pinfunction "2_2") (pintype "unspecified"))
      (node (ref "H4") (pin "2") (pinfunction "2_2") (pintype "unspecified"))
      (node (ref "H6") (pin "2") (pinfunction "2_2") (pintype "unspecified"))
      (node (ref "H7") (pin "1") (pinfunction "1_1") (pintype "unspecified"))
      (node (ref "H7") (pin "3") (pinfunction "3_3") (pintype "unspecified"))
      (node (ref "H7") (pin "5") (pinfunction "5_5") (pintype "unspecified"))
      (node (ref "H8") (pin "1") (pinfunction "1_1") (pintype "unspecified"))
      (node (ref "H8") (pin "3") (pinfunction "3_3") (pintype "unspecified"))
      (node (ref "H8") (pin "5") (pinfunction "5_5") (pintype "unspecified"))
      (node (ref "H9") (pin "1") (pinfunction "1_1") (pintype "unspecified"))
      (node (ref "H9") (pin "3") (pinfunction "3_3") (pintype "unspecified"))
      (node (ref "H9") (pin "5") (pinfunction "5_5") (pintype "unspecified"))
      (node (ref "L1") (pin "1") (pinfunction "1_1") (pintype "unspecified"))
      (node (ref "P1") (pin "3") (pinfunction "3_3") (pintype "unspecified"))
      (node (ref "P19") (pin "1") (pinfunction "1_1") (pintype "unspecified"))
      (node (ref "P2") (pin "3") (pinfunction "3_3") (pintype "unspecified"))
      (node (ref "P20") (pin "1") (pinfunction "1_1") (pintype "unspecified"))
      (node (ref "P21") (pin "1") (pinfunction "1_1") (pintype "unspecified"))
      (node (ref "P21") (pin "2") (pinfunction "2_2") (pintype "unspecified"))
      (node (ref "P23") (pin "1") (pinfunction "1_1") (pintype "unspecified"))
      (node (ref "P3") (pin "3") (pinfunction "3_3") (pintype "unspecified"))
      (node (ref "R1") (pin "2") (pinfunction "2_2") (pintype "unspecified"))
      (node (ref "R11") (pin "1") (pinfunction "1_1") (pintype "unspecified"))
      (node (ref "R36") (pin "2") (pinfunction "2_2") (pintype "input"))
      (node (ref "R4") (pin "2") (pinfunction "2_2") (pintype "unspecified"))
      (node (ref "R6") (pin "2") (pinfunction "2_2") (pintype "unspecified"))
      (node (ref "R8") (pin "2") (pinfunction "2_2") (pintype "unspecified"))
      (node (ref "U1") (pin "3") (pinfunction "FB_3") (pintype "input"))
      (node (ref "U2") (pin "3") (pinfunction "IN_3") (pintype "unspecified"))
      (node (ref "U4") (pin "9") (pinfunction "COM_9") (pintype "unspecified"))
      (node (ref "U5") (pin "5") (pinfunction "VCC_5") (pintype "unspecified"))
      (node (ref "U6") (pin "5") (pinfunction "VCC_5") (pintype "unspecified"))
      (node (ref "U7") (pin "16") (pinfunction "VCC_16") (pintype "unspecified"))
    )
    (net (code "4") (name "24V") (class "Default")
      (node (ref "D1") (pin "1") (pinfunction "1_1") (pintype "unspecified"))
      (node (ref "DC1") (pin "1") (pinfunction "1_1") (pintype "unspecified"))
      (node (ref "P27") (pin "2") (pinfunction "2_2") (pintype "unspecified"))
      (node (ref "R3") (pin "2") (pinfunction "2_2") (pintype "unspecified"))
      (node (ref "R37") (pin "2") (pinfunction "2_2") (pintype "input"))
      (node (ref "R38") (pin "2") (pinfunction "2_2") (pintype "input"))
      (node (ref "R39") (pin "2") (pinfunction "2_2") (pintype "input"))
    )
    (net (code "5") (name "24V_X") (class "Default")
      (node (ref "C17") (pin "1") (pintype "unspecified"))
      (node (ref "H2") (pin "8") (pinfunction "8_8") (pintype "unspecified"))
      (node (ref "P25") (pin "2") (pinfunction "2_2") (pintype "input"))
    )
    (net (code "6") (name "24V_Y") (class "Default")
      (node (ref "C18") (pin "1") (pintype "unspecified"))
      (node (ref "H4") (pin "8") (pinfunction "8_8") (pintype "unspecified"))
      (node (ref "P25") (pin "3") (pinfunction "3_3") (pintype "input"))
    )
    (net (code "7") (name "24V_Z") (class "Default")
      (node (ref "C19") (pin "1") (pintype "unspecified"))
      (node (ref "H6") (pin "8") (pinfunction "8_8") (pintype "unspecified"))
      (node (ref "P24") (pin "2") (pinfunction "2_2") (pintype "unspecified"))
    )
    (net (code "8") (name "48V_SPN+") (class "Default")
      (node (ref "C20") (pin "1") (pintype "unspecified"))
      (node (ref "DZ1") (pin "2") (pinfunction "2_2") (pintype "input"))
      (node (ref "P11") (pin "1") (pinfunction "1_1") (pintype "unspecified"))
      (node (ref "P14") (pin "1") (pinfunction "1_1") (pintype "unspecified"))
      (node (ref "R34") (pin "2") (pinfunction "2_2") (pintype "input"))
    )
    (net (code "9") (name "48V_SPN-") (class "Default")
      (node (ref "C20") (pin "2") (pintype "unspecified"))
      (node (ref "D9") (pin "1") (pinfunction "1_1") (pintype "input"))
      (node (ref "P11") (pin "2") (pinfunction "2_2") (pintype "unspecified"))
      (node (ref "Q1") (pin "3") (pinfunction "S_3") (pintype "unspecified"))
      (node (ref "Q3") (pin "3") (pinfunction "S_3") (pintype "unspecified"))
      (node (ref "R56") (pin "2") (pinfunction "2_2") (pintype "input"))
      (node (ref "R57") (pin "2") (pinfunction "2_2") (pintype "input"))
    )
    (net (code "10") (name "ESP_BOOT") (class "Default")
      (node (ref "Q4") (pin "3") (pinfunction "C_3") (pintype "unspecified"))
      (node (ref "U3") (pin "25") (pinfunction "IO0_25") (pintype "unspecified"))
    )
    (net (code "11") (name "ESP_RST") (class "Default")
      (node (ref "P21") (pin "5") (pinfunction "5_5") (pintype "unspecified"))
      (node (ref "Q5") (pin "3") (pinfunction "C_3") (pintype "unspecified"))
      (node (ref "R18") (pin "1") (pinfunction "1_1") (pintype "input"))
      (node (ref "U3") (pin "3") (pinfunction "EN_3") (pintype "unspecified"))
    )
    (net (code "12") (name "GND") (class "Default")
      (node (ref "C1") (pin "1") (pinfunction "1_1") (pintype "unspecified"))
      (node (ref "C10") (pin "1") (pinfunction "1_1") (pintype "unspecified"))
      (node (ref "C11") (pin "1") (pinfunction "1_1") (pintype "unspecified"))
      (node (ref "C12") (pin "1") (pinfunction "1_1") (pintype "unspecified"))
      (node (ref "C13") (pin "1") (pinfunction "1_1") (pintype "unspecified"))
      (node (ref "C14") (pin "1") (pinfunction "1_1") (pintype "unspecified"))
      (node (ref "C15") (pin "1") (pinfunction "1_1") (pintype "unspecified"))
      (node (ref "C16") (pin "1") (pinfunction "1_1") (pintype "unspecified"))
      (node (ref "C17") (pin "2") (pintype "unspecified"))
      (node (ref "C18") (pin "2") (pintype "unspecified"))
      (node (ref "C19") (pin "2") (pintype "unspecified"))
      (node (ref "C2") (pin "2") (pintype "unspecified"))
      (node (ref "C21") (pin "2") (pinfunction "2_2") (pintype "unspecified"))
      (node (ref "C22") (pin "2") (pintype "unspecified"))
      (node (ref "C23") (pin "2") (pinfunction "2_2") (pintype "unspecified"))
      (node (ref "C24") (pin "2") (pinfunction "2_2") (pintype "unspecified"))
      (node (ref "C25") (pin "2") (pinfunction "2_2") (pintype "unspecified"))
      (node (ref "C26") (pin "1") (pinfunction "1_1") (pintype "unspecified"))
      (node (ref "C27") (pin "2") (pinfunction "2_2") (pintype "unspecified"))
      (node (ref "C3") (pin "1") (pinfunction "1_1") (pintype "unspecified"))
      (node (ref "C4") (pin "1") (pinfunction "1_1") (pintype "unspecified"))
      (node (ref "C5") (pin "2") (pinfunction "2_2") (pintype "input"))
      (node (ref "C6") (pin "1") (pinfunction "1_1") (pintype "unspecified"))
      (node (ref "C7") (pin "2") (pintype "unspecified"))
      (node (ref "C8") (pin "1") (pinfunction "1_1") (pintype "input"))
      (node (ref "C9") (pin "1") (pinfunction "1_1") (pintype "input"))
      (node (ref "D2") (pin "1") (pinfunction "1_1") (pintype "input"))
      (node (ref "D3") (pin "2") (pinfunction "2_2") (pintype "unspecified"))
      (node (ref "D4") (pin "1") (pinfunction "1_1") (pintype "input"))
      (node (ref "D5") (pin "2") (pinfunction "2_2") (pintype "unspecified"))
      (node (ref "D6") (pin "1") (pinfunction "1_1") (pintype "input"))
      (node (ref "D7") (pin "2") (pinfunction "2_2") (pintype "unspecified"))
      (node (ref "DC1") (pin "2") (pinfunction "2_2") (pintype "unspecified"))
      (node (ref "DC1") (pin "3") (pinfunction "3_3") (pintype "unspecified"))
      (node (ref "DZ2") (pin "1") (pinfunction "1_1") (pintype "input"))
      (node (ref "H2") (pin "1") (pinfunction "1_1") (pintype "unspecified"))
      (node (ref "H2") (pin "7") (pinfunction "7_7") (pintype "unspecified"))
      (node (ref "H4") (pin "1") (pinfunction "1_1") (pintype "unspecified"))
      (node (ref "H4") (pin "7") (pinfunction "7_7") (pintype "unspecified"))
      (node (ref "H6") (pin "1") (pinfunction "1_1") (pintype "unspecified"))
      (node (ref "H6") (pin "7") (pinfunction "7_7") (pintype "unspecified"))
      (node (ref "K1") (pin "1") (pinfunction "1_1") (pintype "unspecified"))
      (node (ref "K1") (pin "2") (pinfunction "2_2") (pintype "unspecified"))
      (node (ref "P1") (pin "2") (pinfunction "2_2") (pintype "unspecified"))
      (node (ref "P15") (pin "1") (pinfunction "1_1") (pintype "unspecified"))
      (node (ref "P16") (pin "1") (pinfunction "1_1") (pintype "input"))
      (node (ref "P17") (pin "1") (pinfunction "1_1") (pintype "input"))
      (node (ref "P18") (pin "1") (pinfunction "1_1") (pintype "input"))
      (node (ref "P19") (pin "3") (pinfunction "3_3") (pintype "unspecified"))
      (node (ref "P2") (pin "2") (pinfunction "2_2") (pintype "unspecified"))
      (node (ref "P20") (pin "3") (pinfunction "3_3") (pintype "unspecified"))
      (node (ref "P21") (pin "3") (pinfunction "3_3") (pintype "unspecified"))
      (node (ref "P21") (pin "4") (pinfunction "4_4") (pintype "unspecified"))
      (node (ref "P22") (pin "4") (pinfunction "GND_4") (pintype "unspecified"))
      (node (ref "P22") (pin "5") (pinfunction "GND_5") (pintype "unspecified"))
      (node (ref "P22") (pin "6") (pinfunction "GND_6") (pintype "unspecified"))
      (node (ref "P23") (pin "2") (pinfunction "2_2") (pintype "unspecified"))
      (node (ref "P24") (pin "1") (pinfunction "1_1") (pintype "unspecified"))
      (node (ref "P25") (pin "1") (pinfunction "1_1") (pintype "input"))
      (node (ref "P27") (pin "1") (pinfunction "1_1") (pintype "unspecified"))
      (node (ref "P3") (pin "2") (pinfunction "2_2") (pintype "unspecified"))
      (node (ref "P4") (pin "2") (pintype "input"))
      (node (ref "P5") (pin "2") (pintype "input"))
      (node (ref "P6") (pin "2") (pintype "input"))
      (node (ref "P7") (pin "2") (pintype "input"))
      (node (ref "P8") (pin "2") (pintype "input"))
      (node (ref "Q2") (pin "3") (pinfunction "E_3") (pintype "input"))
      (node (ref "R21") (pin "2") (pinfunction "2_2") (pintype "unspecified"))
      (node (ref "R22") (pin "2") (pinfunction "2_2") (pintype "unspecified"))
      (node (ref "R23") (pin "2") (pinfunction "2_2") (pintype "unspecified"))
      (node (ref "R24") (pin "2") (pinfunction "2_2") (pintype "unspecified"))
      (node (ref "R25") (pin "2") (pinfunction "2_2") (pintype "unspecified"))
      (node (ref "R26") (pin "2") (pinfunction "2_2") (pintype "unspecified"))
      (node (ref "R27") (pin "2") (pinfunction "2_2") (pintype "unspecified"))
      (node (ref "R28") (pin "2") (pinfunction "2_2") (pintype "unspecified"))
      (node (ref "R29") (pin "2") (pinfunction "2_2") (pintype "unspecified"))
      (node (ref "R30") (pin "2") (pinfunction "2_2") (pintype "unspecified"))
      (node (ref "R31") (pin "2") (pinfunction "2_2") (pintype "unspecified"))
      (node (ref "R32") (pin "2") (pinfunction "2_2") (pintype "unspecified"))
      (node (ref "R42") (pin "2") (pinfunction "2_2") (pintype "input"))
      (node (ref "R45") (pin "2") (pinfunction "2_2") (pintype "unspecified"))
      (node (ref "R46") (pin "2") (pinfunction "2_2") (pintype "unspecified"))
      (node (ref "R47") (pin "2") (pinfunction "2_2") (pintype "unspecified"))
      (node (ref "R49") (pin "2") (pinfunction "2_2") (pintype "input"))
      (node (ref "R50") (pin "2") (pinfunction "2_2") (pintype "unspecified"))
      (node (ref "R51") (pin "2") (pinfunction "2_2") (pintype "unspecified"))
      (node (ref "R52") (pin "2") (pinfunction "2_2") (pintype "unspecified"))
      (node (ref "R53") (pin "2") (pinfunction "2_2") (pintype "unspecified"))
      (node (ref "R54") (pin "2") (pinfunction "2_2") (pintype "unspecified"))
      (node (ref "R55") (pin "2") (pinfunction "2_2") (pintype "unspecified"))
      (node (ref "R56") (pin "1") (pinfunction "1_1") (pintype "input"))
      (node (ref "R57") (pin "1") (pinfunction "1_1") (pintype "input"))
      (node (ref "R58") (pin "2") (pinfunction "2_2") (pintype "input"))
      (node (ref "R7") (pin "2") (pinfunction "2_2") (pintype "unspecified"))
      (node (ref "U1") (pin "5") (pinfunction "GND_5") (pintype "input"))
      (node (ref "U1") (pin "6") (pinfunction "GND_6") (pintype "input"))
      (node (ref "U1") (pin "7") (pinfunction "GND_7") (pintype "input"))
      (node (ref "U1") (pin "8") (pinfunction "GND_8") (pintype "input"))
      (node (ref "U2") (pin "1") (pinfunction "GND_1") (pintype "unspecified"))
      (node (ref "U3") (pin "1") (pinfunction "GND_1") (pintype "unspecified"))
      (node (ref "U3") (pin "15") (pinfunction "GND_15") (pintype "unspecified"))
      (node (ref "U3") (pin "38") (pinfunction "GND_38") (pintype "unspecified"))
      (node (ref "U3") (pin "39") (pinfunction "EP_39") (pintype "unspecified"))
      (node (ref "U4") (pin "8") (pinfunction "GND_8") (pintype "unspecified"))
      (node (ref "U5") (pin "3") (pinfunction "GND_3") (pintype "unspecified"))
      (node (ref "U6") (pin "3") (pinfunction "GND_3") (pintype "unspecified"))
      (node (ref "U7") (pin "1") (pinfunction "GND_1") (pintype "unspecified"))
      (node (ref "U8") (pin "10") (pinfunction "GND_10") (pintype "unspecified"))
      (node (ref "U8") (pin "11") (pinfunction "GND_11") (pintype "unspecified"))
      (node (ref "U8") (pin "12") (pinfunction "GND_12") (pintype "unspecified"))
      (node (ref "U8") (pin "13") (pinfunction "GND_13") (pintype "unspecified"))
      (node (ref "U8") (pin "6") (pinfunction "VSS_6") (pintype "unspecified"))
      (node (ref "U9") (pin "2") (pinfunction "2_2") (pintype "unspecified"))
    )
    (net (code "13") (name "HOLD") (class "Default")
      (node (ref "R14") (pin "1") (pinfunction "1_1") (pintype "input"))
      (node (ref "U3") (pin "7") (pinfunction "IO35_7") (pintype "unspecified"))
    )
    (net (code "14") (name "MOTOR_EN") (class "Default")
      (node (ref "U3") (pin "14") (pinfunction "IO12_14") (pintype "unspecified"))
      (node (ref "U4") (pin "1") (pinfunction "IN1_1") (pintype "unspecified"))
    )
    (net (code "15") (name "MX_DIR") (class "Default")
      (node (ref "U3") (pin "12") (pinfunction "IO27_12") (pintype "unspecified"))
      (node (ref "U4") (pin "3") (pinfunction "IN3_3") (pintype "unspecified"))
    )
    (net (code "16") (name "MX_STEP") (class "Default")
      (node (ref "U3") (pin "13") (pinfunction "IO14_13") (pintype "unspecified"))
      (node (ref "U4") (pin "2") (pinfunction "IN2_2") (pintype "unspecified"))
    )
    (net (code "17") (name "MY_DIR") (class "Default")
      (node (ref "U3") (pin "10") (pinfunction "IO25_10") (pintype "unspecified"))
      (node (ref "U4") (pin "5") (pinfunction "IN5_5") (pintype "unspecified"))
    )
    (net (code "18") (name "MY_STEP") (class "Default")
      (node (ref "U3") (pin "11") (pinfunction "IO26_11") (pintype "unspecified"))
      (node (ref "U4") (pin "4") (pinfunction "IN4_4") (pintype "unspecified"))
    )
    (net (code "19") (name "MZ_DIR") (class "Default")
      (node (ref "U3") (pin "8") (pinfunction "IO32_8") (pintype "unspecified"))
      (node (ref "U4") (pin "7") (pinfunction "IN7_7") (pintype "unspecified"))
    )
    (net (code "20") (name "MZ_STEP") (class "Default")
      (node (ref "U3") (pin "9") (pinfunction "IO33_9") (pintype "unspecified"))
      (node (ref "U4") (pin "6") (pinfunction "IN6_6") (pintype "unspecified"))
    )
    (net (code "21") (name "M_EN_O") (class "Default")
      (node (ref "H1") (pin "8") (pinfunction "8_8") (pintype "unspecified"))
      (node (ref "H3") (pin "8") (pinfunction "8_8") (pintype "unspecified"))
      (node (ref "H5") (pin "8") (pinfunction "8_8") (pintype "unspecified"))
      (node (ref "P16") (pin "4") (pinfunction "4_4") (pintype "input"))
      (node (ref "P17") (pin "4") (pinfunction "4_4") (pintype "input"))
      (node (ref "P18") (pin "4") (pinfunction "4_4") (pintype "input"))
      (node (ref "U4") (pin "16") (pinfunction "OUT1_16") (pintype "unspecified"))
    )
    (net (code "22") (name "Net-(C12-Pad2)") (class "Default")
      (node (ref "C12") (pin "2") (pinfunction "2_2") (pintype "unspecified"))
      (node (ref "P4") (pin "1") (pintype "input"))
      (node (ref "R11") (pin "2") (pinfunction "2_2") (pintype "unspecified"))
      (node (ref "R12") (pin "2") (pinfunction "2_2") (pintype "input"))
    )
    (net (code "23") (name "Net-(C13-Pad2)") (class "Default")
      (node (ref "C13") (pin "2") (pinfunction "2_2") (pintype "unspecified"))
      (node (ref "P5") (pin "1") (pintype "input"))
      (node (ref "R13") (pin "2") (pinfunction "2_2") (pintype "unspecified"))
      (node (ref "R14") (pin "2") (pinfunction "2_2") (pintype "input"))
    )
    (net (code "24") (name "Net-(C14-Pad2)") (class "Default")
      (node (ref "C14") (pin "2") (pinfunction "2_2") (pintype "unspecified"))
      (node (ref "K1") (pin "3") (pinfunction "3_3") (pintype "unspecified"))
      (node (ref "K1") (pin "4") (pinfunction "4_4") (pintype "unspecified"))
      (node (ref "P7") (pin "1") (pintype "input"))
      (node (ref "R15") (pin "2") (pinfunction "2_2") (pintype "unspecified"))
      (node (ref "R18") (pin "2") (pinfunction "2_2") (pintype "input"))
    )
    (net (code "25") (name "Net-(C15-Pad2)") (class "Default")
      (node (ref "C15") (pin "2") (pinfunction "2_2") (pintype "unspecified"))
      (node (ref "P8") (pin "1") (pintype "input"))
      (node (ref "R16") (pin "2") (pinfunction "2_2") (pintype "unspecified"))
      (node (ref "R19") (pin "2") (pinfunction "2_2") (pintype "input"))
    )
    (net (code "26") (name "Net-(C16-Pad2)") (class "Default")
      (node (ref "C16") (pin "2") (pinfunction "2_2") (pintype "unspecified"))
      (node (ref "P6") (pin "1") (pintype "input"))
      (node (ref "R17") (pin "2") (pinfunction "2_2") (pintype "unspecified"))
      (node (ref "R20") (pin "2") (pinfunction "2_2") (pintype "input"))
    )
    (net (code "27") (name "Net-(D3-Pad1)") (class "Default")
      (node (ref "D3") (pin "1") (pinfunction "1_1") (pintype "unspecified"))
      (node (ref "R3") (pin "1") (pinfunction "1_1") (pintype "unspecified"))
    )
    (net (code "28") (name "Net-(D5-Pad1)") (class "Default")
      (node (ref "D5") (pin "1") (pinfunction "1_1") (pintype "unspecified"))
      (node (ref "R6") (pin "1") (pinfunction "1_1") (pintype "unspecified"))
    )
    (net (code "29") (name "Net-(D7-Pad1)") (class "Default")
      (node (ref "D7") (pin "1") (pinfunction "1_1") (pintype "unspecified"))
      (node (ref "R10") (pin "1") (pinfunction "1_1") (pintype "unspecified"))
    )
    (net (code "30") (name "Net-(D8-Pad1)") (class "Default")
      (node (ref "D8") (pin "1") (pinfunction "1_1") (pintype "unspecified"))
      (node (ref "R34") (pin "1") (pinfunction "1_1") (pintype "input"))
    )
    (net (code "31") (name "Net-(D10-Pad2)") (class "Default")
      (node (ref "D10") (pin "2") (pinfunction "2_2") (pintype "unspecified"))
      (node (ref "H10") (pin "2") (pinfunction "2_2") (pintype "unspecified"))
    )
    (net (code "32") (name "Net-(H1-Pad3)") (class "Default")
      (node (ref "H1") (pin "3") (pinfunction "3_3") (pintype "unspecified"))
      (node (ref "H1") (pin "4") (pinfunction "4_4") (pintype "unspecified"))
    )
    (net (code "33") (name "Net-(H3-Pad3)") (class "Default")
      (node (ref "H3") (pin "3") (pinfunction "3_3") (pintype "unspecified"))
      (node (ref "H3") (pin "4") (pinfunction "4_4") (pintype "unspecified"))
    )
    (net (code "34") (name "Net-(H5-Pad3)") (class "Default")
      (node (ref "H5") (pin "3") (pinfunction "3_3") (pintype "unspecified"))
      (node (ref "H5") (pin "4") (pinfunction "4_4") (pintype "unspecified"))
    )
    (net (code "35") (name "Net-(P21-Pad6)") (class "Default")
      (node (ref "P21") (pin "6") (pinfunction "6_6") (pintype "unspecified"))
      (node (ref "P23") (pin "3") (pinfunction "3_3") (pintype "unspecified"))
      (node (ref "R65") (pin "2") (pinfunction "2_2") (pintype "unspecified"))
    )
    (net (code "36") (name "Net-(P21-Pad8)") (class "Default")
      (node (ref "P21") (pin "8") (pinfunction "8_8") (pintype "unspecified"))
      (node (ref "P23") (pin "4") (pinfunction "4_4") (pintype "unspecified"))
      (node (ref "R67") (pin "2") (pinfunction "2_2") (pintype "unspecified"))
    )
    (net (code "37") (name "Net-(Q1-D)") (class "Default")
      (node (ref "D8") (pin "2") (pinfunction "2_2") (pintype "unspecified"))
      (node (ref "D9") (pin "2") (pinfunction "2_2") (pintype "input"))
      (node (ref "DZ1") (pin "1") (pinfunction "1_1") (pintype "input"))
      (node (ref "P14") (pin "2") (pinfunction "2_2") (pintype "unspecified"))
      (node (ref "Q1") (pin "2") (pinfunction "D_2") (pintype "unspecified"))
      (node (ref "Q3") (pin "4") (pinfunction "D_4") (pintype "unspecified"))
    )
    (net (code "38") (name "Net-(Q2-B)") (class "Default")
      (node (ref "Q2") (pin "1") (pinfunction "B_1") (pintype "input"))
      (node (ref "R36") (pin "1") (pinfunction "1_1") (pintype "input"))
      (node (ref "R43") (pin "2") (pinfunction "2_2") (pintype "input"))
    )
    (net (code "39") (name "Net-(Q4-B)") (class "Default")
      (node (ref "Q4") (pin "1") (pinfunction "B_1") (pintype "unspecified"))
      (node (ref "R62") (pin "2") (pinfunction "2_2") (pintype "unspecified"))
    )
    (net (code "40") (name "Net-(Q4-E)") (class "Default")
      (node (ref "Q4") (pin "2") (pinfunction "E_2") (pintype "unspecified"))
      (node (ref "R69") (pin "1") (pinfunction "1_1") (pintype "unspecified"))
      (node (ref "U7") (pin "13") (pinfunction "DTR#_13") (pintype "unspecified"))
    )
    (net (code "41") (name "Net-(Q5-B)") (class "Default")
      (node (ref "Q5") (pin "1") (pinfunction "B_1") (pintype "unspecified"))
      (node (ref "R69") (pin "2") (pinfunction "2_2") (pintype "unspecified"))
    )
    (net (code "42") (name "Net-(Q5-E)") (class "Default")
      (node (ref "Q5") (pin "2") (pinfunction "E_2") (pintype "unspecified"))
      (node (ref "R62") (pin "1") (pinfunction "1_1") (pintype "unspecified"))
      (node (ref "U7") (pin "14") (pinfunction "RTS#_14") (pintype "unspecified"))
    )
    (net (code "43") (name "Net-(U1-ON{slash}OFF)") (class "Default")
      (node (ref "R7") (pin "1") (pinfunction "1_1") (pintype "unspecified"))
      (node (ref "U1") (pin "4") (pinfunction "ON/OFF_4") (pintype "input"))
    )
    (net (code "44") (name "Net-(U1-OUTPUT)") (class "Default")
      (node (ref "D2") (pin "2") (pinfunction "2_2") (pintype "input"))
      (node (ref "L1") (pin "2") (pinfunction "2_2") (pintype "unspecified"))
      (node (ref "U1") (pin "2") (pinfunction "OUTPUT_2") (pintype "input"))
    )
    (net (code "45") (name "Net-(U5-A)") (class "Default")
      (node (ref "R40") (pin "2") (pinfunction "2_2") (pintype "input"))
      (node (ref "R41") (pin "2") (pinfunction "2_2") (pintype "input"))
      (node (ref "R42") (pin "1") (pinfunction "1_1") (pintype "input"))
      (node (ref "U5") (pin "2") (pinfunction "A_2") (pintype "unspecified"))
    )
    (net (code "46") (name "Net-(U5-Y)") (class "Default")
      (node (ref "R43") (pin "1") (pinfunction "1_1") (pintype "input"))
      (node (ref "R48") (pin "2") (pinfunction "2_2") (pintype "input"))
      (node (ref "U5") (pin "4") (pinfunction "Y_4") (pintype "unspecified"))
    )
    (net (code "47") (name "Net-(U6-Y)") (class "Default")
      (node (ref "R59") (pin "1") (pinfunction "1_1") (pintype "input"))
      (node (ref "U6") (pin "4") (pinfunction "Y_4") (pintype "unspecified"))
    )
    (net (code "48") (name "Net-(U7-RXD)") (class "Default")
      (node (ref "R61") (pin "1") (pinfunction "1_1") (pintype "unspecified"))
      (node (ref "U7") (pin "3") (pinfunction "RXD_3") (pintype "unspecified"))
    )
    (net (code "49") (name "Net-(U7-TXD)") (class "Default")
      (node (ref "R60") (pin "1") (pinfunction "1_1") (pintype "unspecified"))
      (node (ref "U7") (pin "2") (pinfunction "TXD_2") (pintype "unspecified"))
    )
    (net (code "50") (name "Net-(U7-UD+)") (class "Default")
      (node (ref "U7") (pin "5") (pinfunction "UD+_5") (pintype "unspecified"))
      (node (ref "U9") (pin "6") (pinfunction "6_6") (pintype "unspecified"))
    )
    (net (code "51") (name "Net-(U7-UD-)") (class "Default")
      (node (ref "U7") (pin "6") (pinfunction "UD-_6") (pintype "unspecified"))
      (node (ref "U9") (pin "4") (pinfunction "4_4") (pintype "unspecified"))
    )
    (net (code "52") (name "Net-(U7-V3)") (class "Default")
      (node (ref "C23") (pin "1") (pinfunction "1_1") (pintype "unspecified"))
      (node (ref "U7") (pin "4") (pinfunction "V3_4") (pintype "unspecified"))
    )
    (net (code "53") (name "Net-(U7-XI)") (class "Default")
      (node (ref "C24") (pin "1") (pinfunction "1_1") (pintype "unspecified"))
      (node (ref "U7") (pin "7") (pinfunction "XI_7") (pintype "unspecified"))
      (node (ref "Y1") (pin "2") (pinfunction "OSC2_2") (pintype "unspecified"))
    )
    (net (code "54") (name "Net-(U7-XO)") (class "Default")
      (node (ref "C25") (pin "1") (pinfunction "1_1") (pintype "unspecified"))
      (node (ref "U7") (pin "8") (pinfunction "XO_8") (pintype "unspecified"))
      (node (ref "Y1") (pin "1") (pinfunction "OSC1_1") (pintype "unspecified"))
    )
    (net (code "55") (name "PRE") (class "Default")
      (node (ref "R20") (pin "1") (pinfunction "1_1") (pintype "input"))
      (node (ref "U3") (pin "36") (pinfunction "IO22_36") (pintype "unspecified"))
    )
    (net (code "56") (name "PROBE") (class "Default")
      (node (ref "R12") (pin "1") (pinfunction "1_1") (pintype "input"))
      (node (ref "U3") (pin "23") (pinfunction "IO15_23") (pintype "unspecified"))
    )
    (net (code "57") (name "PWM") (class "Default")
      (node (ref "R40") (pin "1") (pinfunction "1_1") (pintype "input"))
      (node (ref "R58") (pin "1") (pinfunction "1_1") (pintype "input"))
      (node (ref "U3") (pin "16") (pinfunction "IO13_16") (pintype "unspecified"))
      (node (ref "U6") (pin "2") (pinfunction "A_2") (pintype "unspecified"))
    )
    (net (code "58") (name "PWM_5V") (class "Default")
      (node (ref "P19") (pin "2") (pinfunction "2_2") (pintype "unspecified"))
      (node (ref "R48") (pin "1") (pinfunction "1_1") (pintype "input"))
      (node (ref "R59") (pin "2") (pinfunction "2_2") (pintype "input"))
    )
    (net (code "59") (name "QB") (class "Default")
      (node (ref "R41") (pin "1") (pinfunction "1_1") (pintype "input"))
      (node (ref "U3") (pin "26") (pinfunction "IO4_26") (pintype "unspecified"))
    )
    (net (code "60") (name "RUN") (class "Default")
      (node (ref "U3") (pin "24") (pinfunction "IO2_24") (pintype "unspecified"))
    )
    (net (code "61") (name "RXD") (class "Default")
      (node (ref "R60") (pin "2") (pinfunction "2_2") (pintype "unspecified"))
      (node (ref "R67") (pin "1") (pinfunction "1_1") (pintype "unspecified"))
      (node (ref "U3") (pin "34") (pinfunction "RXD0_34") (pintype "unspecified"))
    )
    (net (code "62") (name "RXD2") (class "Default")
      (node (ref "P15") (pin "2") (pinfunction "2_2") (pintype "unspecified"))
      (node (ref "U3") (pin "27") (pinfunction "IO16_27") (pintype "unspecified"))
    )
    (net (code "63") (name "SD_CD") (class "Default")
      (node (ref "R68") (pin "1") (pinfunction "1_1") (pintype "unspecified"))
      (node (ref "U3") (pin "33") (pinfunction "IO21_33") (pintype "unspecified"))
      (node (ref "U8") (pin "9") (pinfunction "CD_9") (pintype "unspecified"))
    )
    (net (code "64") (name "SD_CS") (class "Default")
      (node (ref "R63") (pin "1") (pinfunction "1_1") (pintype "unspecified"))
      (node (ref "U3") (pin "29") (pinfunction "IO5_29") (pintype "unspecified"))
      (node (ref "U8") (pin "2") (pinfunction "CD/DAT3_2") (pintype "unspecified"))
    )
    (net (code "65") (name "SD_MISO") (class "Default")
      (node (ref "R66") (pin "1") (pinfunction "1_1") (pintype "unspecified"))
      (node (ref "U3") (pin "31") (pinfunction "IO19_31") (pintype "unspecified"))
      (node (ref "U8") (pin "7") (pinfunction "DAT0_7") (pintype "unspecified"))
    )
    (net (code "66") (name "SD_MOSI") (class "Default")
      (node (ref "R64") (pin "1") (pinfunction "1_1") (pintype "unspecified"))
      (node (ref "U3") (pin "37") (pinfunction "IO23_37") (pintype "unspecified"))
      (node (ref "U8") (pin "3") (pinfunction "CMD_3") (pintype "unspecified"))
    )
    (net (code "67") (name "SD_SCLK") (class "Default")
      (node (ref "U3") (pin "30") (pinfunction "IO18_30") (pintype "unspecified"))
      (node (ref "U8") (pin "5") (pinfunction "CLX_5") (pintype "unspecified"))
    )
    (net (code "68") (name "SPN_PWM") (class "Default")
      (node (ref "DZ2") (pin "2") (pinfunction "2_2") (pintype "input"))
      (node (ref "P20") (pin "2") (pinfunction "2_2") (pintype "unspecified"))
      (node (ref "Q2") (pin "2") (pinfunction "C_2") (pintype "input"))
      (node (ref "R37") (pin "1") (pinfunction "1_1") (pintype "input"))
      (node (ref "R38") (pin "1") (pinfunction "1_1") (pintype "input"))
      (node (ref "R39") (pin "1") (pinfunction "1_1") (pintype "input"))
      (node (ref "R44") (pin "1") (pinfunction "1_1") (pintype "input"))
      (node (ref "R49") (pin "1") (pinfunction "1_1") (pintype "input"))
    )
    (net (code "69") (name "SPN_PWM_OUT") (class "Default")
      (node (ref "Q1") (pin "1") (pinfunction "G_1") (pintype "unspecified"))
      (node (ref "Q3") (pin "1") (pinfunction "G_1") (pintype "unspecified"))
      (node (ref "R44") (pin "2") (pinfunction "2_2") (pintype "input"))
    )
    (net (code "70") (name "START") (class "Default")
      (node (ref "R19") (pin "1") (pinfunction "1_1") (pintype "input"))
      (node (ref "R35") (pin "2") (pinfunction "2_2") (pintype "input"))
    )
    (net (code "71") (name "TXD") (class "Default")
      (node (ref "R61") (pin "2") (pinfunction "2_2") (pintype "unspecified"))
      (node (ref "R65") (pin "1") (pinfunction "1_1") (pintype "unspecified"))
      (node (ref "U3") (pin "35") (pinfunction "TXD0_35") (pintype "unspecified"))
    )
    (net (code "72") (name "TXD2") (class "Default")
      (node (ref "P15") (pin "3") (pinfunction "3_3") (pintype "unspecified"))
      (node (ref "R35") (pin "1") (pinfunction "1_1") (pintype "input"))
      (node (ref "U3") (pin "28") (pinfunction "IO17_28") (pintype "unspecified"))
    )
    (net (code "73") (name "USB_DM") (class "Default")
      (node (ref "P22") (pin "2") (pinfunction "D-_2") (pintype "unspecified"))
      (node (ref "U9") (pin "3") (pinfunction "3_3") (pintype "unspecified"))
    )
    (net (code "74") (name "USB_DP") (class "Default")
      (node (ref "P22") (pin "3") (pinfunction "D+_3") (pintype "unspecified"))
      (node (ref "U9") (pin "1") (pinfunction "1_1") (pintype "unspecified"))
    )
    (net (code "75") (name "VIN_24V") (class "Default")
      (node (ref "C2") (pin "1") (pintype "unspecified"))
      (node (ref "C3") (pin "2") (pinfunction "2_2") (pintype "unspecified"))
      (node (ref "D1") (pin "2") (pinfunction "2_2") (pintype "unspecified"))
      (node (ref "U1") (pin "1") (pinfunction "VIN_1") (pintype "input"))
    )
    (net (code "76") (name "VUSB") (class "Default")
      (node (ref "D10") (pin "1") (pinfunction "1_1") (pintype "unspecified"))
      (node (ref "P22") (pin "1") (pinfunction "VBUS_1") (pintype "unspecified"))
      (node (ref "U9") (pin "5") (pinfunction "5_5") (pintype "unspecified"))
    )
    (net (code "77") (name "X_1A") (class "Default")
      (node (ref "H2") (pin "4") (pinfunction "4_4") (pintype "unspecified"))
      (node (ref "P10") (pin "3") (pinfunction "3_3") (pintype "unspecified"))
      (node (ref "R25") (pin "1") (pinfunction "1_1") (pintype "unspecified"))
    )
    (net (code "78") (name "X_1B") (class "Default")
      (node (ref "H2") (pin "3") (pinfunction "3_3") (pintype "unspecified"))
      (node (ref "P10") (pin "4") (pinfunction "4_4") (pintype "unspecified"))
      (node (ref "R23") (pin "1") (pinfunction "1_1") (pintype "unspecified"))
    )
    (net (code "79") (name "X_2A") (class "Default")
      (node (ref "H2") (pin "5") (pinfunction "5_5") (pintype "unspecified"))
      (node (ref "P10") (pin "2") (pinfunction "2_2") (pintype "unspecified"))
      (node (ref "R28") (pin "1") (pinfunction "1_1") (pintype "unspecified"))
    )
    (net (code "80") (name "X_2B") (class "Default")
      (node (ref "H2") (pin "6") (pinfunction "6_6") (pintype "unspecified"))
      (node (ref "P10") (pin "1") (pinfunction "1_1") (pintype "unspecified"))
      (node (ref "R30") (pin "1") (pinfunction "1_1") (pintype "unspecified"))
    )
    (net (code "81") (name "X_DIR_O") (class "Default")
      (node (ref "H1") (pin "1") (pinfunction "1_1") (pintype "unspecified"))
      (node (ref "P16") (pin "2") (pinfunction "2_2") (pintype "input"))
      (node (ref "U4") (pin "14") (pinfunction "OUT3_14") (pintype "unspecified"))
    )
    (net (code "82") (name "X_DIV1") (class "Default")
      (node (ref "H1") (pin "5") (pinfunction "5_5") (pintype "unspecified"))
      (node (ref "H7") (pin "2") (pinfunction "2_2") (pintype "unspecified"))
      (node (ref "R45") (pin "1") (pinfunction "1_1") (pintype "unspecified"))
    )
    (net (code "83") (name "X_DIV2") (class "Default")
      (node (ref "H1") (pin "6") (pinfunction "6_6") (pintype "unspecified"))
      (node (ref "H7") (pin "4") (pinfunction "4_4") (pintype "unspecified"))
      (node (ref "R46") (pin "1") (pinfunction "1_1") (pintype "unspecified"))
    )
    (net (code "84") (name "X_DIV3") (class "Default")
      (node (ref "H1") (pin "7") (pinfunction "7_7") (pintype "unspecified"))
      (node (ref "H7") (pin "6") (pinfunction "6_6") (pintype "unspecified"))
      (node (ref "R50") (pin "1") (pinfunction "1_1") (pintype "unspecified"))
    )
    (net (code "85") (name "X_LIMT") (class "Default")
      (node (ref "R2") (pin "2") (pinfunction "2_2") (pintype "unspecified"))
      (node (ref "U3") (pin "6") (pinfunction "IO34_6") (pintype "unspecified"))
    )
    (net (code "86") (name "X_LIMT_I") (class "Default")
      (node (ref "C1") (pin "2") (pinfunction "2_2") (pintype "unspecified"))
      (node (ref "P1") (pin "1") (pinfunction "1_1") (pintype "unspecified"))
      (node (ref "R1") (pin "1") (pinfunction "1_1") (pintype "unspecified"))
      (node (ref "R2") (pin "1") (pinfunction "1_1") (pintype "unspecified"))
    )
    (net (code "87") (name "X_STEP_O") (class "Default")
      (node (ref "H1") (pin "2") (pinfunction "2_2") (pintype "unspecified"))
      (node (ref "P16") (pin "3") (pinfunction "3_3") (pintype "input"))
      (node (ref "U4") (pin "15") (pinfunction "OUT2_15") (pintype "unspecified"))
    )
    (net (code "88") (name "Y_1A") (class "Default")
      (node (ref "H4") (pin "4") (pinfunction "4_4") (pintype "unspecified"))
      (node (ref "P13") (pin "2") (pinfunction "2_2") (pintype "unspecified"))
      (node (ref "P9") (pin "3") (pinfunction "3_3") (pintype "unspecified"))
      (node (ref "R22") (pin "1") (pinfunction "1_1") (pintype "unspecified"))
    )
    (net (code "89") (name "Y_1B") (class "Default")
      (node (ref "H4") (pin "3") (pinfunction "3_3") (pintype "unspecified"))
      (node (ref "P13") (pin "1") (pinfunction "1_1") (pintype "unspecified"))
      (node (ref "P9") (pin "4") (pinfunction "4_4") (pintype "unspecified"))
      (node (ref "R21") (pin "1") (pinfunction "1_1") (pintype "unspecified"))
    )
    (net (code "90") (name "Y_2A") (class "Default")
      (node (ref "H4") (pin "5") (pinfunction "5_5") (pintype "unspecified"))
      (node (ref "P13") (pin "3") (pinfunction "3_3") (pintype "unspecified"))
      (node (ref "P9") (pin "2") (pinfunction "2_2") (pintype "unspecified"))
      (node (ref "R24") (pin "1") (pinfunction "1_1") (pintype "unspecified"))
    )
    (net (code "91") (name "Y_2B") (class "Default")
      (node (ref "H4") (pin "6") (pinfunction "6_6") (pintype "unspecified"))
      (node (ref "P13") (pin "4") (pinfunction "4_4") (pintype "unspecified"))
      (node (ref "P9") (pin "1") (pinfunction "1_1") (pintype "unspecified"))
      (node (ref "R26") (pin "1") (pinfunction "1_1") (pintype "unspecified"))
    )
    (net (code "92") (name "Y_DIR_O") (class "Default")
      (node (ref "H3") (pin "1") (pinfunction "1_1") (pintype "unspecified"))
      (node (ref "P17") (pin "2") (pinfunction "2_2") (pintype "input"))
      (node (ref "U4") (pin "12") (pinfunction "OUT5_12") (pintype "unspecified"))
    )
    (net (code "93") (name "Y_DIV1") (class "Default")
      (node (ref "H3") (pin "5") (pinfunction "5_5") (pintype "unspecified"))
      (node (ref "H8") (pin "2") (pinfunction "2_2") (pintype "unspecified"))
      (node (ref "R47") (pin "1") (pinfunction "1_1") (pintype "unspecified"))
    )
    (net (code "94") (name "Y_DIV2") (class "Default")
      (node (ref "H3") (pin "6") (pinfunction "6_6") (pintype "unspecified"))
      (node (ref "H8") (pin "4") (pinfunction "4_4") (pintype "unspecified"))
      (node (ref "R51") (pin "1") (pinfunction "1_1") (pintype "unspecified"))
    )
    (net (code "95") (name "Y_DIV3") (class "Default")
      (node (ref "H3") (pin "7") (pinfunction "7_7") (pintype "unspecified"))
      (node (ref "H8") (pin "6") (pinfunction "6_6") (pintype "unspecified"))
      (node (ref "R53") (pin "1") (pinfunction "1_1") (pintype "unspecified"))
    )
    (net (code "96") (name "Y_LIMT") (class "Default")
      (node (ref "R5") (pin "2") (pinfunction "2_2") (pintype "unspecified"))
      (node (ref "U3") (pin "5") (pinfunction "SENSOR_VN_5") (pintype "unspecified"))
    )
    (net (code "97") (name "Y_LIMT_I") (class "Default")
      (node (ref "C4") (pin "2") (pinfunction "2_2") (pintype "unspecified"))
      (node (ref "P2") (pin "1") (pinfunction "1_1") (pintype "unspecified"))
      (node (ref "R4") (pin "1") (pinfunction "1_1") (pintype "unspecified"))
      (node (ref "R5") (pin "1") (pinfunction "1_1") (pintype "unspecified"))
    )
    (net (code "98") (name "Y_STEP_O") (class "Default")
      (node (ref "H3") (pin "2") (pinfunction "2_2") (pintype "unspecified"))
      (node (ref "P17") (pin "3") (pinfunction "3_3") (pintype "input"))
      (node (ref "U4") (pin "13") (pinfunction "OUT4_13") (pintype "unspecified"))
    )
    (net (code "99") (name "Z_1A") (class "Default")
      (node (ref "H6") (pin "4") (pinfunction "4_4") (pintype "unspecified"))
      (node (ref "P12") (pin "3") (pinfunction "3_3") (pintype "unspecified"))
      (node (ref "R29") (pin "1") (pinfunction "1_1") (pintype "unspecified"))
    )
    (net (code "100") (name "Z_1B") (class "Default")
      (node (ref "H6") (pin "3") (pinfunction "3_3") (pintype "unspecified"))
      (node (ref "P12") (pin "4") (pinfunction "4_4") (pintype "unspecified"))
      (node (ref "R27") (pin "1") (pinfunction "1_1") (pintype "unspecified"))
    )
    (net (code "101") (name "Z_2A") (class "Default")
      (node (ref "H6") (pin "5") (pinfunction "5_5") (pintype "unspecified"))
      (node (ref "P12") (pin "2") (pinfunction "2_2") (pintype "unspecified"))
      (node (ref "R31") (pin "1") (pinfunction "1_1") (pintype "unspecified"))
    )
    (net (code "102") (name "Z_2B") (class "Default")
      (node (ref "H6") (pin "6") (pinfunction "6_6") (pintype "unspecified"))
      (node (ref "P12") (pin "1") (pinfunction "1_1") (pintype "unspecified"))
      (node (ref "R32") (pin "1") (pinfunction "1_1") (pintype "unspecified"))
    )
    (net (code "103") (name "Z_DIR_O") (class "Default")
      (node (ref "H5") (pin "1") (pinfunction "1_1") (pintype "unspecified"))
      (node (ref "P18") (pin "2") (pinfunction "2_2") (pintype "input"))
      (node (ref "U4") (pin "10") (pinfunction "OUT7_10") (pintype "unspecified"))
    )
    (net (code "104") (name "Z_DIV1") (class "Default")
      (node (ref "H5") (pin "5") (pinfunction "5_5") (pintype "unspecified"))
      (node (ref "H9") (pin "2") (pinfunction "2_2") (pintype "unspecified"))
      (node (ref "R52") (pin "1") (pinfunction "1_1") (pintype "unspecified"))
    )
    (net (code "105") (name "Z_DIV2") (class "Default")
      (node (ref "H5") (pin "6") (pinfunction "6_6") (pintype "unspecified"))
      (node (ref "H9") (pin "4") (pinfunction "4_4") (pintype "unspecified"))
      (node (ref "R54") (pin "1") (pinfunction "1_1") (pintype "unspecified"))
    )
    (net (code "106") (name "Z_DIV3") (class "Default")
      (node (ref "H5") (pin "7") (pinfunction "7_7") (pintype "unspecified"))
      (node (ref "H9") (pin "6") (pinfunction "6_6") (pintype "unspecified"))
      (node (ref "R55") (pin "1") (pinfunction "1_1") (pintype "unspecified"))
    )
    (net (code "107") (name "Z_LIMT") (class "Default")
      (node (ref "R9") (pin "2") (pinfunction "2_2") (pintype "unspecified"))
      (node (ref "U3") (pin "4") (pinfunction "SENSOR_VP_4") (pintype "unspecified"))
    )
    (net (code "108") (name "Z_LIMT_I") (class "Default")
      (node (ref "C11") (pin "2") (pinfunction "2_2") (pintype "unspecified"))
      (node (ref "P3") (pin "1") (pinfunction "1_1") (pintype "unspecified"))
      (node (ref "R8") (pin "1") (pinfunction "1_1") (pintype "unspecified"))
      (node (ref "R9") (pin "1") (pinfunction "1_1") (pintype "unspecified"))
    )
    (net (code "109") (name "Z_STEP_O") (class "Default")
      (node (ref "H5") (pin "2") (pinfunction "2_2") (pintype "unspecified"))
      (node (ref "P18") (pin "3") (pinfunction "3_3") (pintype "input"))
      (node (ref "U4") (pin "11") (pinfunction "OUT6_11") (pintype "unspecified"))
    )
    (net (code "110") (name "unconnected-(P21-Pad7)") (class "Default")
      (node (ref "P21") (pin "7") (pinfunction "7_7") (pintype "unspecified"))
    )
    (net (code "111") (name "unconnected-(U3-CLK-Pad20)") (class "Default")
      (node (ref "U3") (pin "20") (pinfunction "CLK_20") (pintype "unspecified"))
    )
    (net (code "112") (name "unconnected-(U3-CMD-Pad19)") (class "Default")
      (node (ref "U3") (pin "19") (pinfunction "CMD_19") (pintype "unspecified"))
    )
    (net (code "113") (name "unconnected-(U3-NC-Pad32)") (class "Default")
      (node (ref "U3") (pin "32") (pinfunction "NC_32") (pintype "unspecified"))
    )
    (net (code "114") (name "unconnected-(U3-SD0-Pad21)") (class "Default")
      (node (ref "U3") (pin "21") (pinfunction "SD0_21") (pintype "unspecified"))
    )
    (net (code "115") (name "unconnected-(U3-SD1-Pad22)") (class "Default")
      (node (ref "U3") (pin "22") (pinfunction "SD1_22") (pintype "unspecified"))
    )
    (net (code "116") (name "unconnected-(U3-SD2-Pad17)") (class "Default")
      (node (ref "U3") (pin "17") (pinfunction "SD2_17") (pintype "unspecified"))
    )
    (net (code "117") (name "unconnected-(U3-SD3-Pad18)") (class "Default")
      (node (ref "U3") (pin "18") (pinfunction "SD3_18") (pintype "unspecified"))
    )
    (net (code "118") (name "unconnected-(U5-NC-Pad1)") (class "Default")
      (node (ref "U5") (pin "1") (pinfunction "NC_1") (pintype "unspecified"))
    )
    (net (code "119") (name "unconnected-(U6-NC-Pad1)") (class "Default")
      (node (ref "U6") (pin "1") (pinfunction "NC_1") (pintype "unspecified"))
    )
    (net (code "120") (name "unconnected-(U7-CTS#-Pad9)") (class "Default")
      (node (ref "U7") (pin "9") (pinfunction "CTS#_9") (pintype "unspecified"))
    )
    (net (code "121") (name "unconnected-(U7-DCD#-Pad12)") (class "Default")
      (node (ref "U7") (pin "12") (pinfunction "DCD#_12") (pintype "unspecified"))
    )
    (net (code "122") (name "unconnected-(U7-DSR#-Pad10)") (class "Default")
      (node (ref "U7") (pin "10") (pinfunction "DSR#_10") (pintype "unspecified"))
    )
    (net (code "123") (name "unconnected-(U7-R232-Pad15)") (class "Default")
      (node (ref "U7") (pin "15") (pinfunction "R232_15") (pintype "unspecified"))
    )
    (net (code "124") (name "unconnected-(U7-RI#-Pad11)") (class "Default")
      (node (ref "U7") (pin "11") (pinfunction "RI#_11") (pintype "unspecified"))
    )
    (net (code "125") (name "unconnected-(U8-DAT1-Pad8)") (class "Default")
      (node (ref "U8") (pin "8") (pinfunction "DAT1_8") (pintype "unspecified"))
    )
    (net (code "126") (name "unconnected-(U8-DAT2-Pad1)") (class "Default")
      (node (ref "U8") (pin "1") (pinfunction "DAT2_1") (pintype "unspecified"))
    )
  )
)
